# rPi_vsynth.net
KiCad netlist of a schematic drawn in EAGLE
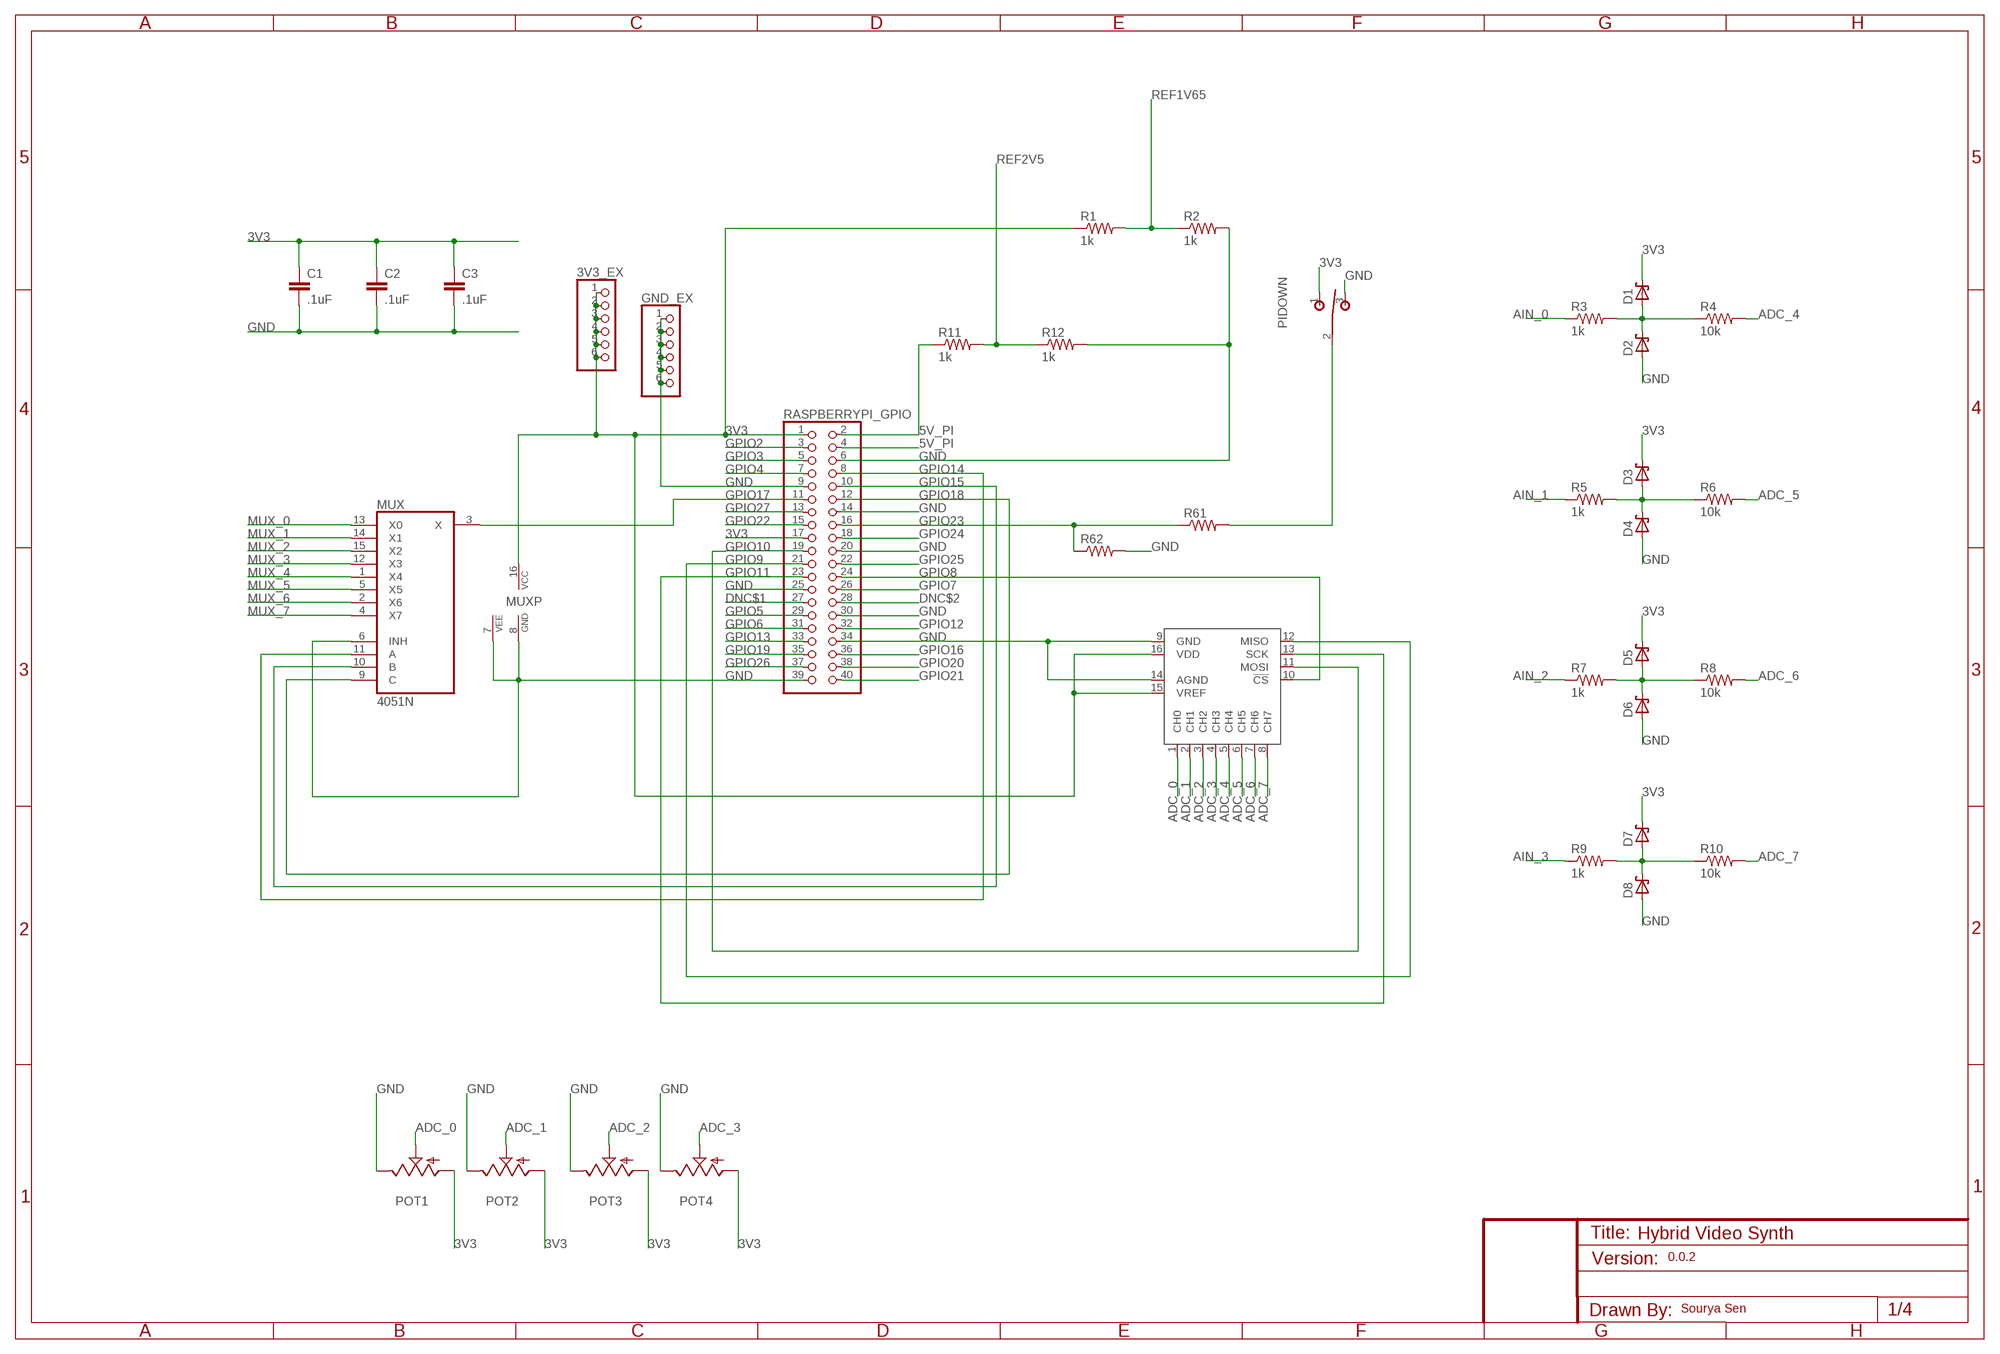
[diagram p0: schematic, sheet 1]
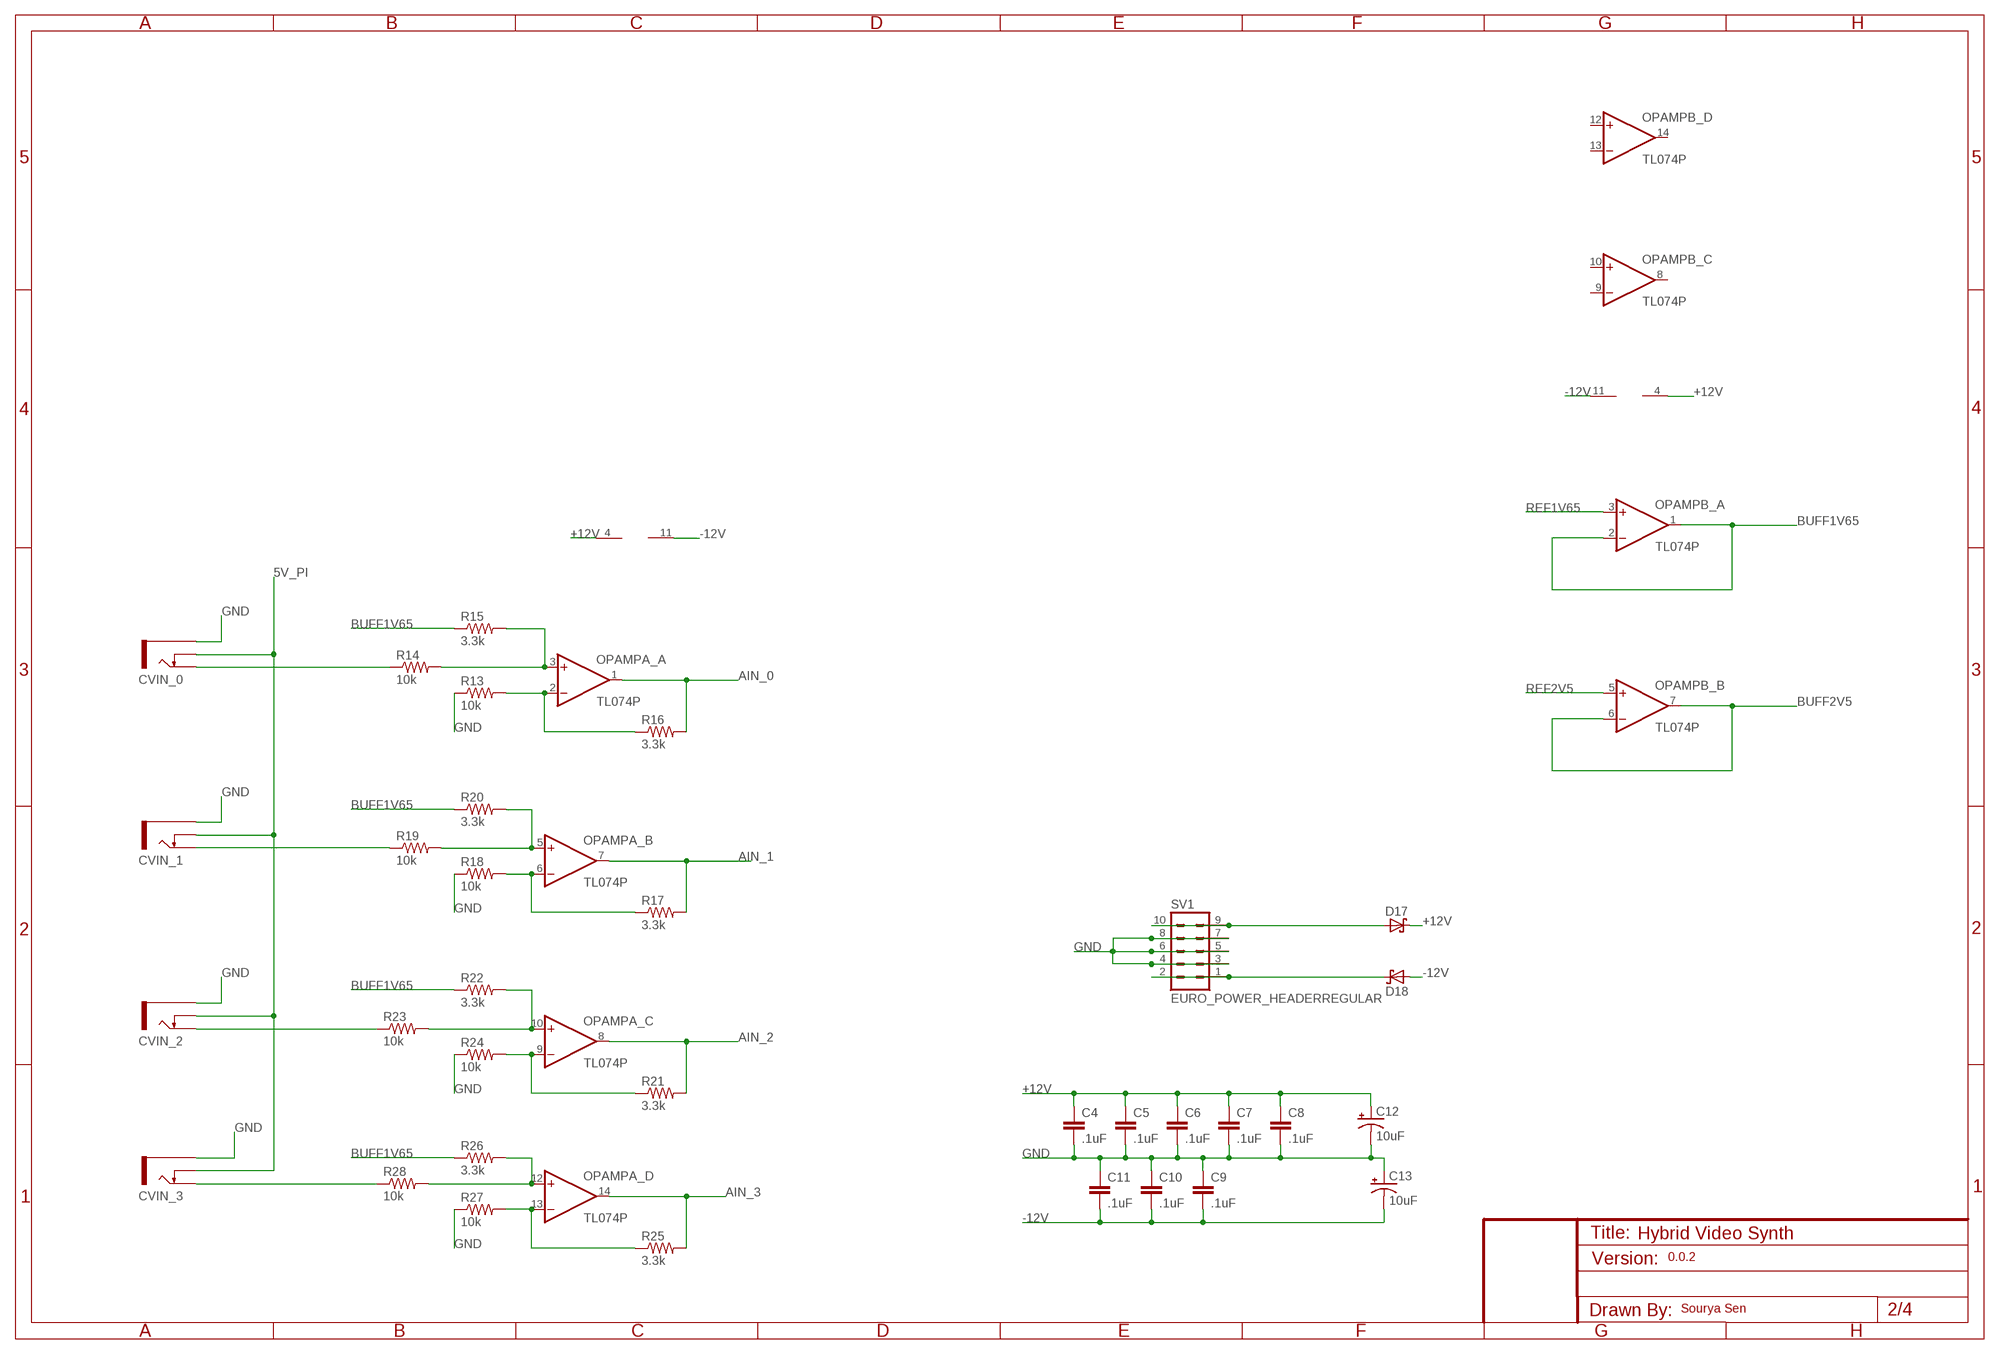
[diagram p1: schematic, sheet 2]
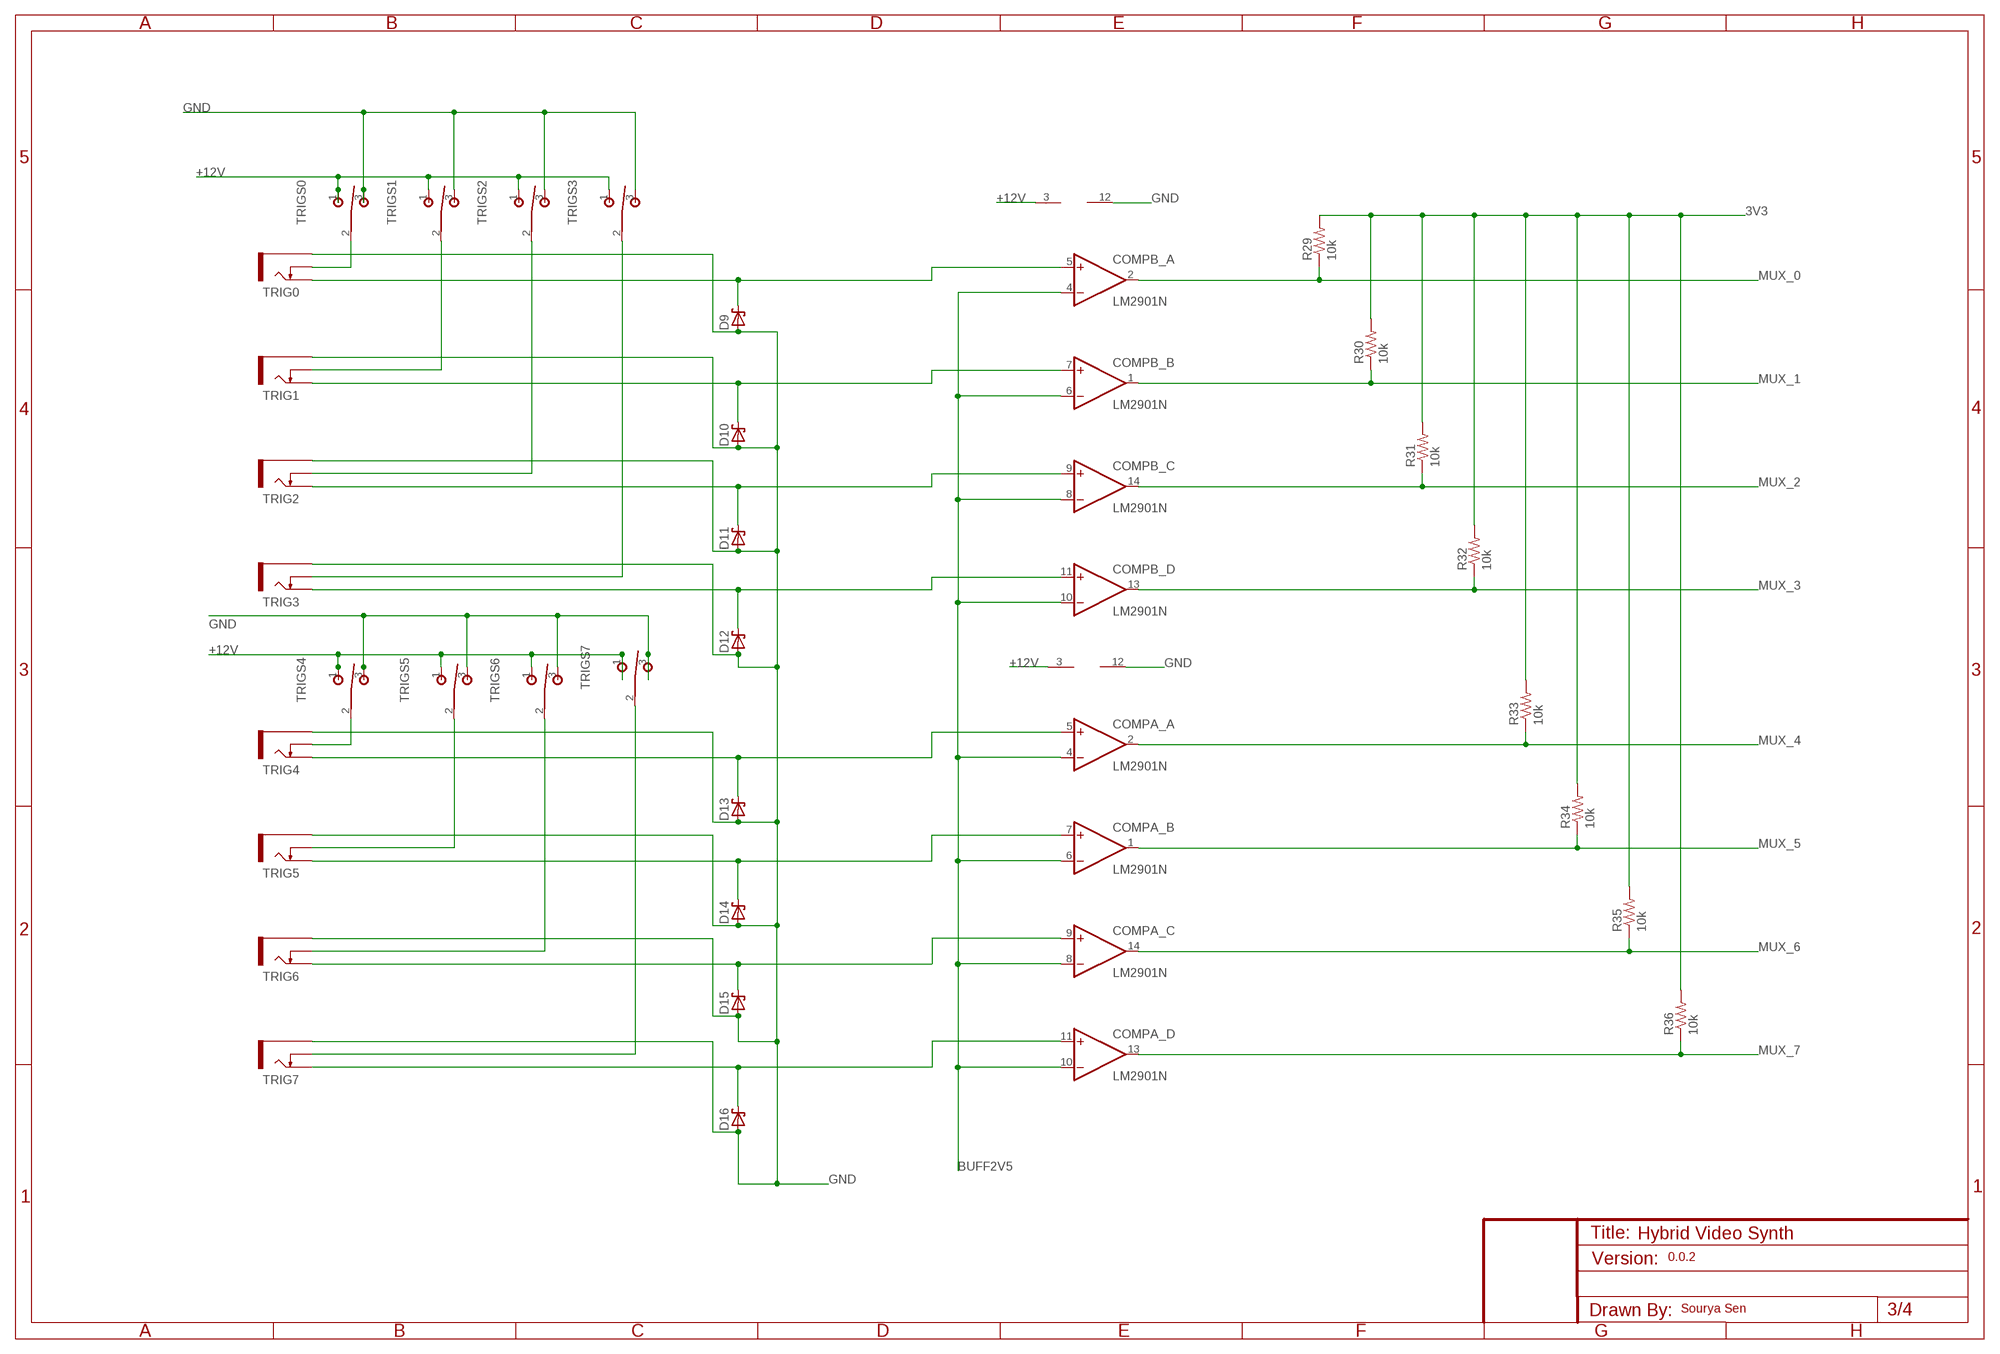
[diagram p2: schematic, sheet 3]
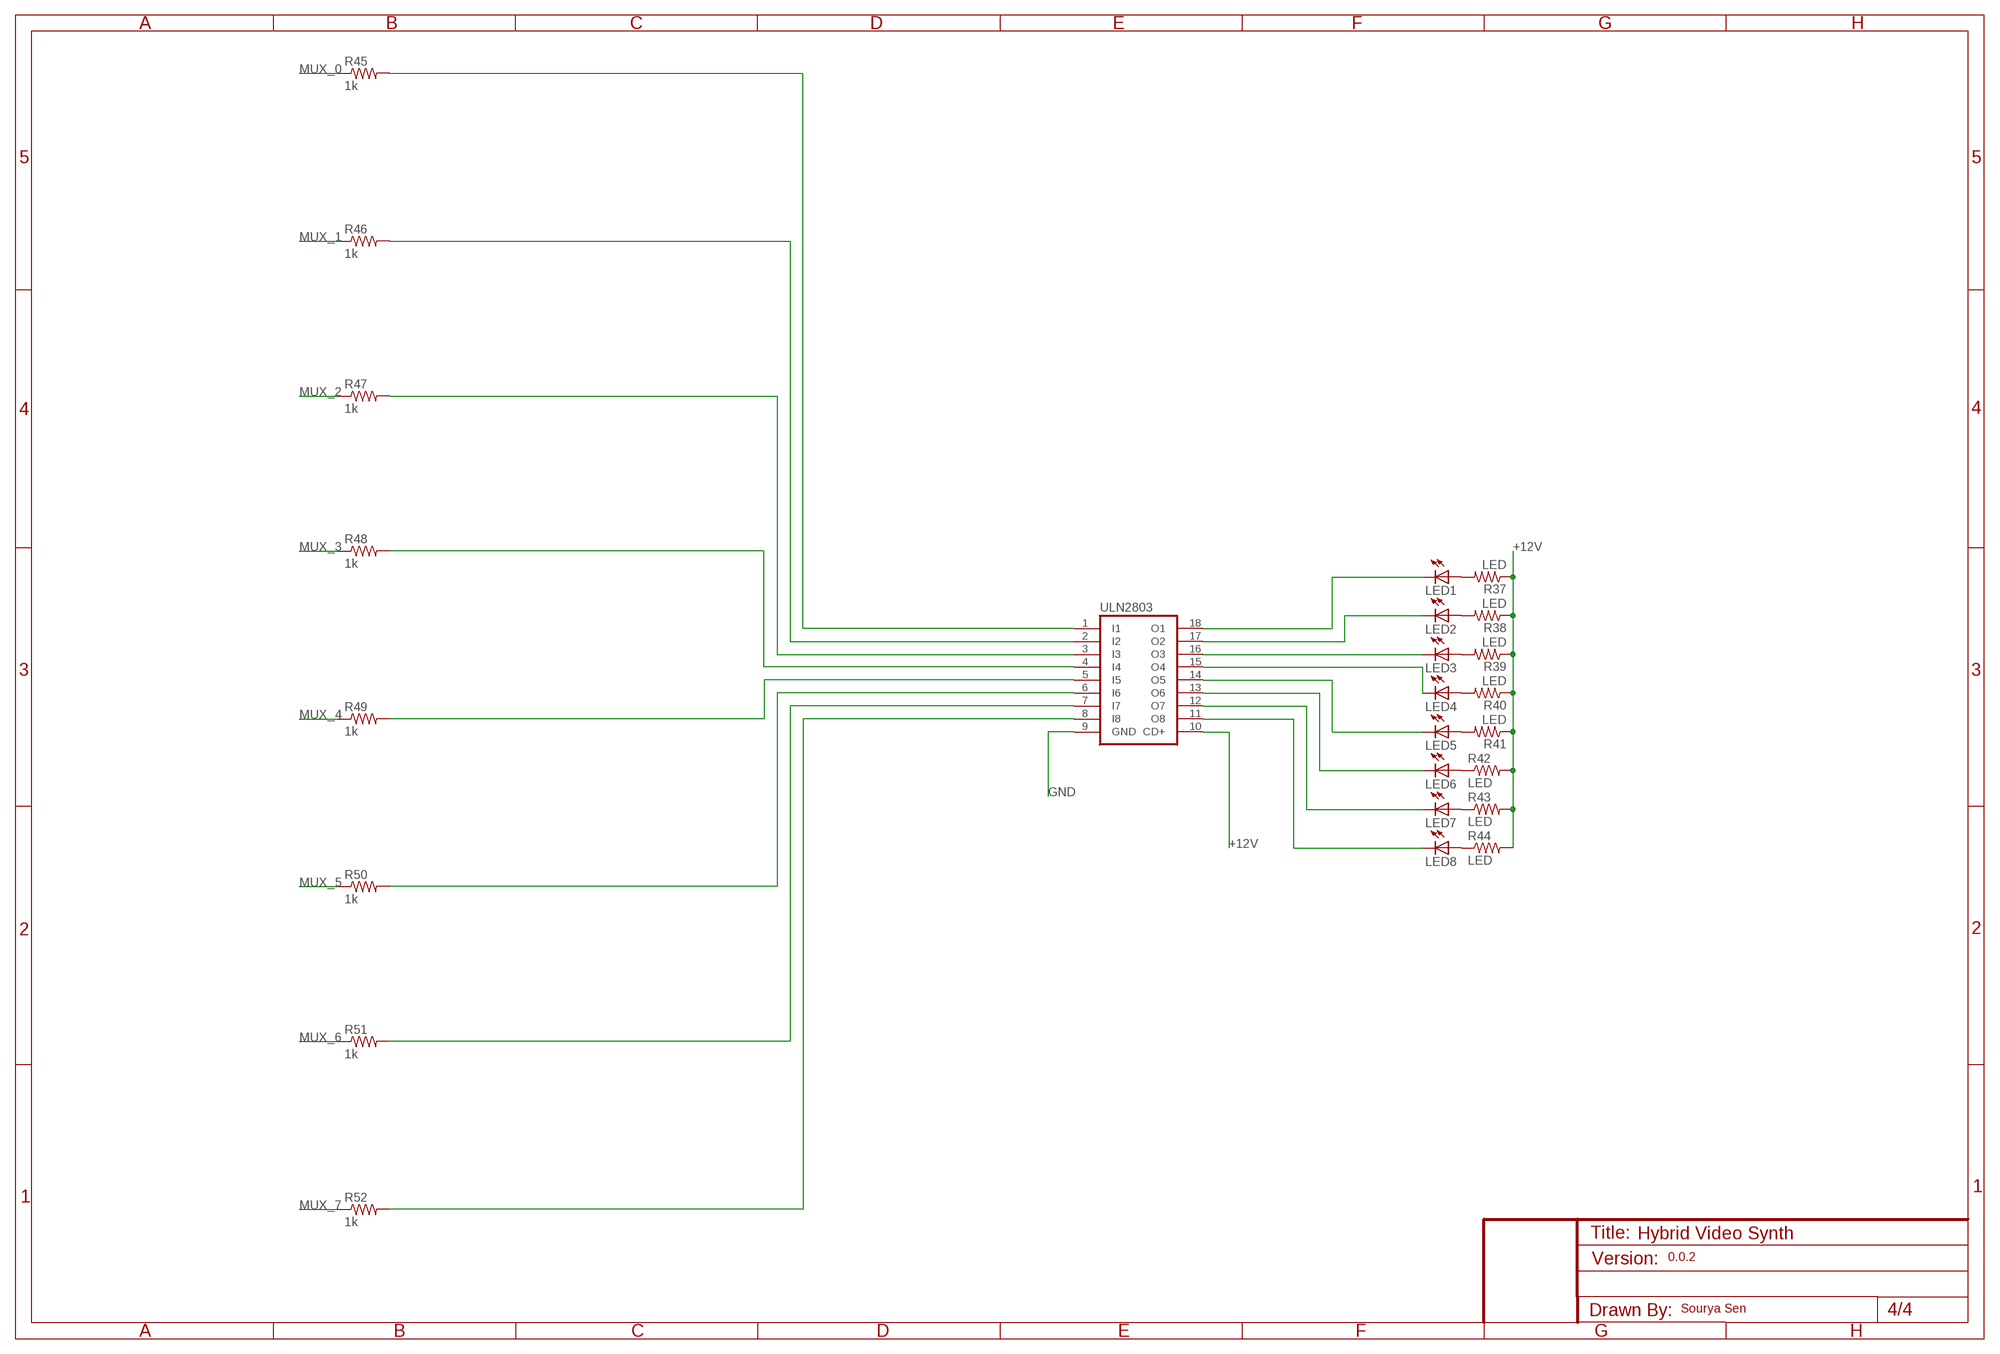
[diagram p3: schematic, sheet 4]

(export (version "E")
  (design (tool "Eeschema 10.0.6"))
  (components
    (comp (ref "3V3_EX")
      (value "PINHD-1X6B")
      (footprint "eagle-import:1X06-BIG")
      (libsource (lib "eagle-import") (part "PINHD-1X6B"))
    )
    (comp (ref "C1")
      (value ".1uF")
      (footprint "eagle-import:CAP-PTH-SMALL2")
      (libsource (lib "eagle-import") (part "CAPPTH2"))
    )
    (comp (ref "C2")
      (value ".1uF")
      (footprint "eagle-import:CAP-PTH-SMALL2")
      (libsource (lib "eagle-import") (part "CAPPTH2"))
    )
    (comp (ref "C3")
      (value ".1uF")
      (footprint "eagle-import:CAP-PTH-SMALL2")
      (libsource (lib "eagle-import") (part "CAPPTH2"))
    )
    (comp (ref "D1")
      (value "SCHOTTKY-DIODEDO35-7")
      (footprint "eagle-import:DO35-7")
      (libsource (lib "eagle-import") (part "SCHOTTKY-DIODEDO35-7"))
    )
    (comp (ref "D2")
      (value "SCHOTTKY-DIODEDO35-7")
      (footprint "eagle-import:DO35-7")
      (libsource (lib "eagle-import") (part "SCHOTTKY-DIODEDO35-7"))
    )
    (comp (ref "D3")
      (value "SCHOTTKY-DIODEDO35-7")
      (footprint "eagle-import:DO35-7")
      (libsource (lib "eagle-import") (part "SCHOTTKY-DIODEDO35-7"))
    )
    (comp (ref "D4")
      (value "SCHOTTKY-DIODEDO35-7")
      (footprint "eagle-import:DO35-7")
      (libsource (lib "eagle-import") (part "SCHOTTKY-DIODEDO35-7"))
    )
    (comp (ref "D5")
      (value "SCHOTTKY-DIODEDO35-7")
      (footprint "eagle-import:DO35-7")
      (libsource (lib "eagle-import") (part "SCHOTTKY-DIODEDO35-7"))
    )
    (comp (ref "D6")
      (value "SCHOTTKY-DIODEDO35-7")
      (footprint "eagle-import:DO35-7")
      (libsource (lib "eagle-import") (part "SCHOTTKY-DIODEDO35-7"))
    )
    (comp (ref "D7")
      (value "SCHOTTKY-DIODEDO35-7")
      (footprint "eagle-import:DO35-7")
      (libsource (lib "eagle-import") (part "SCHOTTKY-DIODEDO35-7"))
    )
    (comp (ref "D8")
      (value "SCHOTTKY-DIODEDO35-7")
      (footprint "eagle-import:DO35-7")
      (libsource (lib "eagle-import") (part "SCHOTTKY-DIODEDO35-7"))
    )
    (comp (ref "GND_EX")
      (value "PINHD-1X6B")
      (footprint "eagle-import:1X06-BIG")
      (libsource (lib "eagle-import") (part "PINHD-1X6B"))
    )
    (comp (ref "MCP3008")
      (value "MCP3008P")
      (footprint "eagle-import:DIL16")
      (libsource (lib "eagle-import") (part "MCP3008P"))
    )
    (comp (ref "MUX")
      (value "4051N")
      (footprint "eagle-import:DIL16")
      (libsource (lib "eagle-import") (part "4051N"))
    )
    (comp (ref "PIDOWN")
      (value "T-80-T-SPDT-ON-OFF-ON")
      (footprint "eagle-import:M9040P")
      (libsource (lib "eagle-import") (part "T-80-T-SPDT-ON-OFF-ON"))
    )
    (comp (ref "POT1")
      (value "9MM_SNAP-IN_POT_")
      (footprint "eagle-import:9MM_SNAP-IN_POT")
      (libsource (lib "eagle-import") (part "9MM_SNAP-IN_POT_"))
    )
    (comp (ref "POT2")
      (value "9MM_SNAP-IN_POT_")
      (footprint "eagle-import:9MM_SNAP-IN_POT")
      (libsource (lib "eagle-import") (part "9MM_SNAP-IN_POT_"))
    )
    (comp (ref "POT3")
      (value "9MM_SNAP-IN_POT_")
      (footprint "eagle-import:9MM_SNAP-IN_POT")
      (libsource (lib "eagle-import") (part "9MM_SNAP-IN_POT_"))
    )
    (comp (ref "POT4")
      (value "9MM_SNAP-IN_POT_")
      (footprint "eagle-import:9MM_SNAP-IN_POT")
      (libsource (lib "eagle-import") (part "9MM_SNAP-IN_POT_"))
    )
    (comp (ref "R1")
      (value "1k")
      (footprint "eagle-import:AXIAL-0.4")
      (libsource (lib "eagle-import") (part "RESISTORPTH-1/4W"))
    )
    (comp (ref "R2")
      (value "1k")
      (footprint "eagle-import:AXIAL-0.4")
      (libsource (lib "eagle-import") (part "RESISTORPTH-1/4W"))
    )
    (comp (ref "R3")
      (value "1k")
      (footprint "eagle-import:AXIAL-0.4")
      (libsource (lib "eagle-import") (part "RESISTORPTH-1/4W"))
    )
    (comp (ref "R4")
      (value "10k")
      (footprint "eagle-import:AXIAL-0.4")
      (libsource (lib "eagle-import") (part "RESISTORPTH-1/4W"))
    )
    (comp (ref "R5")
      (value "1k")
      (footprint "eagle-import:AXIAL-0.4")
      (libsource (lib "eagle-import") (part "RESISTORPTH-1/4W"))
    )
    (comp (ref "R6")
      (value "10k")
      (footprint "eagle-import:AXIAL-0.4")
      (libsource (lib "eagle-import") (part "RESISTORPTH-1/4W"))
    )
    (comp (ref "R7")
      (value "1k")
      (footprint "eagle-import:AXIAL-0.4")
      (libsource (lib "eagle-import") (part "RESISTORPTH-1/4W"))
    )
    (comp (ref "R8")
      (value "10k")
      (footprint "eagle-import:AXIAL-0.4")
      (libsource (lib "eagle-import") (part "RESISTORPTH-1/4W"))
    )
    (comp (ref "R9")
      (value "1k")
      (footprint "eagle-import:AXIAL-0.4")
      (libsource (lib "eagle-import") (part "RESISTORPTH-1/4W"))
    )
    (comp (ref "R10")
      (value "10k")
      (footprint "eagle-import:AXIAL-0.4")
      (libsource (lib "eagle-import") (part "RESISTORPTH-1/4W"))
    )
    (comp (ref "R11")
      (value "1k")
      (footprint "eagle-import:AXIAL-0.4")
      (libsource (lib "eagle-import") (part "RESISTORPTH-1/4W"))
    )
    (comp (ref "R12")
      (value "1k")
      (footprint "eagle-import:AXIAL-0.4")
      (libsource (lib "eagle-import") (part "RESISTORPTH-1/4W"))
    )
    (comp (ref "R61")
      (value "RESISTORPTH-1/4W")
      (footprint "eagle-import:AXIAL-0.4")
      (libsource (lib "eagle-import") (part "RESISTORPTH-1/4W"))
    )
    (comp (ref "R62")
      (value "RESISTORPTH-1/4W")
      (footprint "eagle-import:AXIAL-0.4")
      (libsource (lib "eagle-import") (part "RESISTORPTH-1/4W"))
    )
    (comp (ref "RASPBERRYPI_GPIO")
      (value "PINHD-2X20")
      (footprint "eagle-import:2X20")
      (libsource (lib "eagle-import") (part "PINHD-2X20"))
    )
    (comp (ref "C4")
      (value ".1uF")
      (footprint "eagle-import:CAP-PTH-SMALL2")
      (libsource (lib "eagle-import") (part "CAPPTH2"))
    )
    (comp (ref "C5")
      (value ".1uF")
      (footprint "eagle-import:CAP-PTH-SMALL2")
      (libsource (lib "eagle-import") (part "CAPPTH2"))
    )
    (comp (ref "C6")
      (value ".1uF")
      (footprint "eagle-import:CAP-PTH-SMALL2")
      (libsource (lib "eagle-import") (part "CAPPTH2"))
    )
    (comp (ref "C7")
      (value ".1uF")
      (footprint "eagle-import:CAP-PTH-SMALL2")
      (libsource (lib "eagle-import") (part "CAPPTH2"))
    )
    (comp (ref "C8")
      (value ".1uF")
      (footprint "eagle-import:CAP-PTH-SMALL2")
      (libsource (lib "eagle-import") (part "CAPPTH2"))
    )
    (comp (ref "C9")
      (value ".1uF")
      (footprint "eagle-import:CAP-PTH-SMALL2")
      (libsource (lib "eagle-import") (part "CAPPTH2"))
    )
    (comp (ref "C10")
      (value ".1uF")
      (footprint "eagle-import:CAP-PTH-SMALL2")
      (libsource (lib "eagle-import") (part "CAPPTH2"))
    )
    (comp (ref "C11")
      (value ".1uF")
      (footprint "eagle-import:CAP-PTH-SMALL2")
      (libsource (lib "eagle-import") (part "CAPPTH2"))
    )
    (comp (ref "C12")
      (value "10uF")
      (footprint "eagle-import:CPOL-RADIAL-10UF-25V")
      (libsource (lib "eagle-import") (part "CAP_POLPTH2"))
    )
    (comp (ref "C13")
      (value "10uF")
      (footprint "eagle-import:CPOL-RADIAL-10UF-25V")
      (libsource (lib "eagle-import") (part "CAP_POLPTH2"))
    )
    (comp (ref "CVIN_0")
      (value "THONKICONNOLD")
      (footprint "eagle-import:THONKICONN")
      (libsource (lib "eagle-import") (part "THONKICONNOLD"))
    )
    (comp (ref "CVIN_1")
      (value "THONKICONNOLD")
      (footprint "eagle-import:THONKICONN")
      (libsource (lib "eagle-import") (part "THONKICONNOLD"))
    )
    (comp (ref "CVIN_2")
      (value "THONKICONNOLD")
      (footprint "eagle-import:THONKICONN")
      (libsource (lib "eagle-import") (part "THONKICONNOLD"))
    )
    (comp (ref "CVIN_3")
      (value "THONKICONNOLD")
      (footprint "eagle-import:THONKICONN")
      (libsource (lib "eagle-import") (part "THONKICONNOLD"))
    )
    (comp (ref "D17")
      (value "SCHOTTKY-DIODEDO35-7")
      (footprint "eagle-import:DO35-7")
      (libsource (lib "eagle-import") (part "SCHOTTKY-DIODEDO35-7"))
    )
    (comp (ref "D18")
      (value "SCHOTTKY-DIODEDO35-7")
      (footprint "eagle-import:DO35-7")
      (libsource (lib "eagle-import") (part "SCHOTTKY-DIODEDO35-7"))
    )
    (comp (ref "OPAMPA_")
      (value "TL074P")
      (footprint "eagle-import:DIL14")
      (libsource (lib "eagle-import") (part "TL074P"))
    )
    (comp (ref "OPAMPB_")
      (value "TL074P")
      (footprint "eagle-import:DIL14")
      (libsource (lib "eagle-import") (part "TL074P"))
    )
    (comp (ref "R13")
      (value "10k")
      (footprint "eagle-import:AXIAL-0.4")
      (libsource (lib "eagle-import") (part "RESISTORPTH-1/4W"))
    )
    (comp (ref "R14")
      (value "10k")
      (footprint "eagle-import:AXIAL-0.4")
      (libsource (lib "eagle-import") (part "RESISTORPTH-1/4W"))
    )
    (comp (ref "R15")
      (value "3.3k")
      (footprint "eagle-import:AXIAL-0.4")
      (libsource (lib "eagle-import") (part "RESISTORPTH-1/4W"))
    )
    (comp (ref "R16")
      (value "3.3k")
      (footprint "eagle-import:AXIAL-0.4")
      (libsource (lib "eagle-import") (part "RESISTORPTH-1/4W"))
    )
    (comp (ref "R17")
      (value "3.3k")
      (footprint "eagle-import:AXIAL-0.4")
      (libsource (lib "eagle-import") (part "RESISTORPTH-1/4W"))
    )
    (comp (ref "R18")
      (value "10k")
      (footprint "eagle-import:AXIAL-0.4")
      (libsource (lib "eagle-import") (part "RESISTORPTH-1/4W"))
    )
    (comp (ref "R19")
      (value "10k")
      (footprint "eagle-import:AXIAL-0.4")
      (libsource (lib "eagle-import") (part "RESISTORPTH-1/4W"))
    )
    (comp (ref "R20")
      (value "3.3k")
      (footprint "eagle-import:AXIAL-0.4")
      (libsource (lib "eagle-import") (part "RESISTORPTH-1/4W"))
    )
    (comp (ref "R21")
      (value "3.3k")
      (footprint "eagle-import:AXIAL-0.4")
      (libsource (lib "eagle-import") (part "RESISTORPTH-1/4W"))
    )
    (comp (ref "R22")
      (value "3.3k")
      (footprint "eagle-import:AXIAL-0.4")
      (libsource (lib "eagle-import") (part "RESISTORPTH-1/4W"))
    )
    (comp (ref "R23")
      (value "10k")
      (footprint "eagle-import:AXIAL-0.4")
      (libsource (lib "eagle-import") (part "RESISTORPTH-1/4W"))
    )
    (comp (ref "R24")
      (value "10k")
      (footprint "eagle-import:AXIAL-0.4")
      (libsource (lib "eagle-import") (part "RESISTORPTH-1/4W"))
    )
    (comp (ref "R25")
      (value "3.3k")
      (footprint "eagle-import:AXIAL-0.4")
      (libsource (lib "eagle-import") (part "RESISTORPTH-1/4W"))
    )
    (comp (ref "R26")
      (value "3.3k")
      (footprint "eagle-import:AXIAL-0.4")
      (libsource (lib "eagle-import") (part "RESISTORPTH-1/4W"))
    )
    (comp (ref "R27")
      (value "10k")
      (footprint "eagle-import:AXIAL-0.4")
      (libsource (lib "eagle-import") (part "RESISTORPTH-1/4W"))
    )
    (comp (ref "R28")
      (value "10k")
      (footprint "eagle-import:AXIAL-0.4")
      (libsource (lib "eagle-import") (part "RESISTORPTH-1/4W"))
    )
    (comp (ref "SV1")
      (value "EURO_POWER_HEADERREGULAR")
      (footprint "eagle-import:EURO_POWER_HEADER")
      (libsource (lib "eagle-import") (part "EURO_POWER_HEADERREGULAR"))
    )
    (comp (ref "COMPA_")
      (value "LM2901N")
      (footprint "eagle-import:DIL14")
      (libsource (lib "eagle-import") (part "LM2901N"))
    )
    (comp (ref "COMPB_")
      (value "LM2901N")
      (footprint "eagle-import:DIL14")
      (libsource (lib "eagle-import") (part "LM2901N"))
    )
    (comp (ref "D9")
      (value "SCHOTTKY-DIODEDO35-7")
      (footprint "eagle-import:DO35-7")
      (libsource (lib "eagle-import") (part "SCHOTTKY-DIODEDO35-7"))
    )
    (comp (ref "D10")
      (value "SCHOTTKY-DIODEDO35-7")
      (footprint "eagle-import:DO35-7")
      (libsource (lib "eagle-import") (part "SCHOTTKY-DIODEDO35-7"))
    )
    (comp (ref "D11")
      (value "SCHOTTKY-DIODEDO35-7")
      (footprint "eagle-import:DO35-7")
      (libsource (lib "eagle-import") (part "SCHOTTKY-DIODEDO35-7"))
    )
    (comp (ref "D12")
      (value "SCHOTTKY-DIODEDO35-7")
      (footprint "eagle-import:DO35-7")
      (libsource (lib "eagle-import") (part "SCHOTTKY-DIODEDO35-7"))
    )
    (comp (ref "D13")
      (value "SCHOTTKY-DIODEDO35-7")
      (footprint "eagle-import:DO35-7")
      (libsource (lib "eagle-import") (part "SCHOTTKY-DIODEDO35-7"))
    )
    (comp (ref "D14")
      (value "SCHOTTKY-DIODEDO35-7")
      (footprint "eagle-import:DO35-7")
      (libsource (lib "eagle-import") (part "SCHOTTKY-DIODEDO35-7"))
    )
    (comp (ref "D15")
      (value "SCHOTTKY-DIODEDO35-7")
      (footprint "eagle-import:DO35-7")
      (libsource (lib "eagle-import") (part "SCHOTTKY-DIODEDO35-7"))
    )
    (comp (ref "D16")
      (value "SCHOTTKY-DIODEDO35-7")
      (footprint "eagle-import:DO35-7")
      (libsource (lib "eagle-import") (part "SCHOTTKY-DIODEDO35-7"))
    )
    (comp (ref "R29")
      (value "10k")
      (footprint "eagle-import:AXIAL-0.4")
      (libsource (lib "eagle-import") (part "RESISTORPTH-1/4W"))
    )
    (comp (ref "R30")
      (value "10k")
      (footprint "eagle-import:AXIAL-0.4")
      (libsource (lib "eagle-import") (part "RESISTORPTH-1/4W"))
    )
    (comp (ref "R31")
      (value "10k")
      (footprint "eagle-import:AXIAL-0.4")
      (libsource (lib "eagle-import") (part "RESISTORPTH-1/4W"))
    )
    (comp (ref "R32")
      (value "10k")
      (footprint "eagle-import:AXIAL-0.4")
      (libsource (lib "eagle-import") (part "RESISTORPTH-1/4W"))
    )
    (comp (ref "R33")
      (value "10k")
      (footprint "eagle-import:AXIAL-0.4")
      (libsource (lib "eagle-import") (part "RESISTORPTH-1/4W"))
    )
    (comp (ref "R34")
      (value "10k")
      (footprint "eagle-import:AXIAL-0.4")
      (libsource (lib "eagle-import") (part "RESISTORPTH-1/4W"))
    )
    (comp (ref "R35")
      (value "10k")
      (footprint "eagle-import:AXIAL-0.4")
      (libsource (lib "eagle-import") (part "RESISTORPTH-1/4W"))
    )
    (comp (ref "R36")
      (value "10k")
      (footprint "eagle-import:AXIAL-0.4")
      (libsource (lib "eagle-import") (part "RESISTORPTH-1/4W"))
    )
    (comp (ref "TRIG0")
      (value "THONKICONNOLD")
      (footprint "eagle-import:THONKICONN")
      (libsource (lib "eagle-import") (part "THONKICONNOLD"))
    )
    (comp (ref "TRIG1")
      (value "THONKICONNOLD")
      (footprint "eagle-import:THONKICONN")
      (libsource (lib "eagle-import") (part "THONKICONNOLD"))
    )
    (comp (ref "TRIG2")
      (value "THONKICONNOLD")
      (footprint "eagle-import:THONKICONN")
      (libsource (lib "eagle-import") (part "THONKICONNOLD"))
    )
    (comp (ref "TRIG3")
      (value "THONKICONNOLD")
      (footprint "eagle-import:THONKICONN")
      (libsource (lib "eagle-import") (part "THONKICONNOLD"))
    )
    (comp (ref "TRIG4")
      (value "THONKICONNOLD")
      (footprint "eagle-import:THONKICONN")
      (libsource (lib "eagle-import") (part "THONKICONNOLD"))
    )
    (comp (ref "TRIG5")
      (value "THONKICONNOLD")
      (footprint "eagle-import:THONKICONN")
      (libsource (lib "eagle-import") (part "THONKICONNOLD"))
    )
    (comp (ref "TRIG6")
      (value "THONKICONNOLD")
      (footprint "eagle-import:THONKICONN")
      (libsource (lib "eagle-import") (part "THONKICONNOLD"))
    )
    (comp (ref "TRIG7")
      (value "THONKICONNOLD")
      (footprint "eagle-import:THONKICONN")
      (libsource (lib "eagle-import") (part "THONKICONNOLD"))
    )
    (comp (ref "TRIGS0")
      (value "T-80-T-SPDT-ON-OFF-ON")
      (footprint "eagle-import:M9040P")
      (libsource (lib "eagle-import") (part "T-80-T-SPDT-ON-OFF-ON"))
    )
    (comp (ref "TRIGS1")
      (value "T-80-T-SPDT-ON-OFF-ON")
      (footprint "eagle-import:M9040P")
      (libsource (lib "eagle-import") (part "T-80-T-SPDT-ON-OFF-ON"))
    )
    (comp (ref "TRIGS2")
      (value "T-80-T-SPDT-ON-OFF-ON")
      (footprint "eagle-import:M9040P")
      (libsource (lib "eagle-import") (part "T-80-T-SPDT-ON-OFF-ON"))
    )
    (comp (ref "TRIGS3")
      (value "T-80-T-SPDT-ON-OFF-ON")
      (footprint "eagle-import:M9040P")
      (libsource (lib "eagle-import") (part "T-80-T-SPDT-ON-OFF-ON"))
    )
    (comp (ref "TRIGS4")
      (value "T-80-T-SPDT-ON-OFF-ON")
      (footprint "eagle-import:M9040P")
      (libsource (lib "eagle-import") (part "T-80-T-SPDT-ON-OFF-ON"))
    )
    (comp (ref "TRIGS5")
      (value "T-80-T-SPDT-ON-OFF-ON")
      (footprint "eagle-import:M9040P")
      (libsource (lib "eagle-import") (part "T-80-T-SPDT-ON-OFF-ON"))
    )
    (comp (ref "TRIGS6")
      (value "T-80-T-SPDT-ON-OFF-ON")
      (footprint "eagle-import:M9040P")
      (libsource (lib "eagle-import") (part "T-80-T-SPDT-ON-OFF-ON"))
    )
    (comp (ref "TRIGS7")
      (value "T-80-T-SPDT-ON-OFF-ON")
      (footprint "eagle-import:M9040P")
      (libsource (lib "eagle-import") (part "T-80-T-SPDT-ON-OFF-ON"))
    )
    (comp (ref "LED1")
      (value "LED3MM")
      (footprint "eagle-import:LED3MM")
      (libsource (lib "eagle-import") (part "LED3MM"))
    )
    (comp (ref "LED2")
      (value "LED3MM")
      (footprint "eagle-import:LED3MM")
      (libsource (lib "eagle-import") (part "LED3MM"))
    )
    (comp (ref "LED3")
      (value "LED3MM")
      (footprint "eagle-import:LED3MM")
      (libsource (lib "eagle-import") (part "LED3MM"))
    )
    (comp (ref "LED4")
      (value "LED3MM")
      (footprint "eagle-import:LED3MM")
      (libsource (lib "eagle-import") (part "LED3MM"))
    )
    (comp (ref "LED5")
      (value "LED3MM")
      (footprint "eagle-import:LED3MM")
      (libsource (lib "eagle-import") (part "LED3MM"))
    )
    (comp (ref "LED6")
      (value "LED3MM")
      (footprint "eagle-import:LED3MM")
      (libsource (lib "eagle-import") (part "LED3MM"))
    )
    (comp (ref "LED7")
      (value "LED3MM")
      (footprint "eagle-import:LED3MM")
      (libsource (lib "eagle-import") (part "LED3MM"))
    )
    (comp (ref "LED8")
      (value "LED3MM")
      (footprint "eagle-import:LED3MM")
      (libsource (lib "eagle-import") (part "LED3MM"))
    )
    (comp (ref "R37")
      (value "LED")
      (footprint "eagle-import:AXIAL-0.4")
      (libsource (lib "eagle-import") (part "RESISTORPTH-1/4W"))
    )
    (comp (ref "R38")
      (value "LED")
      (footprint "eagle-import:AXIAL-0.4")
      (libsource (lib "eagle-import") (part "RESISTORPTH-1/4W"))
    )
    (comp (ref "R39")
      (value "LED")
      (footprint "eagle-import:AXIAL-0.4")
      (libsource (lib "eagle-import") (part "RESISTORPTH-1/4W"))
    )
    (comp (ref "R40")
      (value "LED")
      (footprint "eagle-import:AXIAL-0.4")
      (libsource (lib "eagle-import") (part "RESISTORPTH-1/4W"))
    )
    (comp (ref "R41")
      (value "LED")
      (footprint "eagle-import:AXIAL-0.4")
      (libsource (lib "eagle-import") (part "RESISTORPTH-1/4W"))
    )
    (comp (ref "R42")
      (value "LED")
      (footprint "eagle-import:AXIAL-0.4")
      (libsource (lib "eagle-import") (part "RESISTORPTH-1/4W"))
    )
    (comp (ref "R43")
      (value "LED")
      (footprint "eagle-import:AXIAL-0.4")
      (libsource (lib "eagle-import") (part "RESISTORPTH-1/4W"))
    )
    (comp (ref "R44")
      (value "LED")
      (footprint "eagle-import:AXIAL-0.4")
      (libsource (lib "eagle-import") (part "RESISTORPTH-1/4W"))
    )
    (comp (ref "R45")
      (value "1k")
      (footprint "eagle-import:AXIAL-0.4")
      (libsource (lib "eagle-import") (part "RESISTORPTH-1/4W"))
    )
    (comp (ref "R46")
      (value "1k")
      (footprint "eagle-import:AXIAL-0.4")
      (libsource (lib "eagle-import") (part "RESISTORPTH-1/4W"))
    )
    (comp (ref "R47")
      (value "1k")
      (footprint "eagle-import:AXIAL-0.4")
      (libsource (lib "eagle-import") (part "RESISTORPTH-1/4W"))
    )
    (comp (ref "R48")
      (value "1k")
      (footprint "eagle-import:AXIAL-0.4")
      (libsource (lib "eagle-import") (part "RESISTORPTH-1/4W"))
    )
    (comp (ref "R49")
      (value "1k")
      (footprint "eagle-import:AXIAL-0.4")
      (libsource (lib "eagle-import") (part "RESISTORPTH-1/4W"))
    )
    (comp (ref "R50")
      (value "1k")
      (footprint "eagle-import:AXIAL-0.4")
      (libsource (lib "eagle-import") (part "RESISTORPTH-1/4W"))
    )
    (comp (ref "R51")
      (value "1k")
      (footprint "eagle-import:AXIAL-0.4")
      (libsource (lib "eagle-import") (part "RESISTORPTH-1/4W"))
    )
    (comp (ref "R52")
      (value "1k")
      (footprint "eagle-import:AXIAL-0.4")
      (libsource (lib "eagle-import") (part "RESISTORPTH-1/4W"))
    )
    (comp (ref "ULN2803")
      (value "ULN2803A")
      (footprint "eagle-import:DIL18")
      (libsource (lib "eagle-import") (part "ULN2803A"))
    )
  )
  (nets
    (net (code "1") (name "+12V") (class "Default")
      (node (ref "C12") (pin "1") (pinfunction "+_1") (pintype "passive"))
      (node (ref "C4") (pin "1") (pinfunction "1_1") (pintype "passive"))
      (node (ref "C5") (pin "1") (pinfunction "1_1") (pintype "passive"))
      (node (ref "C6") (pin "1") (pinfunction "1_1") (pintype "passive"))
      (node (ref "C7") (pin "1") (pinfunction "1_1") (pintype "passive"))
      (node (ref "C8") (pin "1") (pinfunction "1_1") (pintype "passive"))
      (node (ref "COMPA_") (pin "3") (pinfunction "V+_3") (pintype "power_in"))
      (node (ref "COMPB_") (pin "3") (pinfunction "V+_3") (pintype "power_in"))
      (node (ref "D17") (pin "C") (pinfunction "C_C") (pintype "passive"))
      (node (ref "OPAMPA_") (pin "4") (pinfunction "V+_4") (pintype "power_in"))
      (node (ref "OPAMPB_") (pin "4") (pinfunction "V+_4") (pintype "power_in"))
      (node (ref "R37") (pin "P$1") (pinfunction "1_P$1") (pintype "passive"))
      (node (ref "R38") (pin "P$1") (pinfunction "1_P$1") (pintype "passive"))
      (node (ref "R39") (pin "P$1") (pinfunction "1_P$1") (pintype "passive"))
      (node (ref "R40") (pin "P$1") (pinfunction "1_P$1") (pintype "passive"))
      (node (ref "R41") (pin "P$1") (pinfunction "1_P$1") (pintype "passive"))
      (node (ref "R42") (pin "P$2") (pinfunction "2_P$2") (pintype "passive"))
      (node (ref "R43") (pin "P$2") (pinfunction "2_P$2") (pintype "passive"))
      (node (ref "R44") (pin "P$2") (pinfunction "2_P$2") (pintype "passive"))
      (node (ref "TRIGS0") (pin "1") (pinfunction "O_1") (pintype "passive"))
      (node (ref "TRIGS1") (pin "1") (pinfunction "O_1") (pintype "passive"))
      (node (ref "TRIGS2") (pin "1") (pinfunction "O_1") (pintype "passive"))
      (node (ref "TRIGS3") (pin "1") (pinfunction "O_1") (pintype "passive"))
      (node (ref "TRIGS4") (pin "1") (pinfunction "O_1") (pintype "passive"))
      (node (ref "TRIGS5") (pin "1") (pinfunction "O_1") (pintype "passive"))
      (node (ref "TRIGS6") (pin "1") (pinfunction "O_1") (pintype "passive"))
      (node (ref "TRIGS7") (pin "1") (pinfunction "O_1") (pintype "passive"))
      (node (ref "ULN2803") (pin "10") (pinfunction "CD+_10") (pintype "passive"))
    )
    (net (code "2") (name "-12V") (class "Default")
      (node (ref "C10") (pin "2") (pinfunction "2_2") (pintype "passive"))
      (node (ref "C11") (pin "2") (pinfunction "2_2") (pintype "passive"))
      (node (ref "C13") (pin "2") (pinfunction "-_2") (pintype "passive"))
      (node (ref "C9") (pin "2") (pinfunction "2_2") (pintype "passive"))
      (node (ref "D18") (pin "A") (pinfunction "A_A") (pintype "passive"))
      (node (ref "OPAMPA_") (pin "11") (pinfunction "V-_11") (pintype "power_in"))
      (node (ref "OPAMPB_") (pin "11") (pinfunction "V-_11") (pintype "power_in"))
    )
    (net (code "3") (name "3V3") (class "Default")
      (node (ref "3V3_EX") (pin "1") (pinfunction "1_1") (pintype "passive"))
      (node (ref "3V3_EX") (pin "2") (pinfunction "2_2") (pintype "passive"))
      (node (ref "3V3_EX") (pin "3") (pinfunction "3_3") (pintype "passive"))
      (node (ref "3V3_EX") (pin "4") (pinfunction "4_4") (pintype "passive"))
      (node (ref "3V3_EX") (pin "5") (pinfunction "5_5") (pintype "passive"))
      (node (ref "3V3_EX") (pin "6") (pinfunction "6_6") (pintype "passive"))
      (node (ref "C1") (pin "1") (pinfunction "1_1") (pintype "passive"))
      (node (ref "C2") (pin "1") (pinfunction "1_1") (pintype "passive"))
      (node (ref "C3") (pin "1") (pinfunction "1_1") (pintype "passive"))
      (node (ref "D1") (pin "C") (pinfunction "C_C") (pintype "passive"))
      (node (ref "D3") (pin "C") (pinfunction "C_C") (pintype "passive"))
      (node (ref "D5") (pin "C") (pinfunction "C_C") (pintype "passive"))
      (node (ref "D7") (pin "C") (pinfunction "C_C") (pintype "passive"))
      (node (ref "MCP3008") (pin "15") (pinfunction "VREF_15") (pintype "power_in"))
      (node (ref "MCP3008") (pin "16") (pinfunction "VDD_16") (pintype "power_in"))
      (node (ref "MUX") (pin "16") (pinfunction "VCC_16") (pintype "power_in"))
      (node (ref "PIDOWN") (pin "1") (pinfunction "O_1") (pintype "passive"))
      (node (ref "POT1") (pin "1") (pinfunction "A_1") (pintype "passive"))
      (node (ref "POT2") (pin "1") (pinfunction "A_1") (pintype "passive"))
      (node (ref "POT3") (pin "1") (pinfunction "A_1") (pintype "passive"))
      (node (ref "POT4") (pin "1") (pinfunction "A_1") (pintype "passive"))
      (node (ref "R1") (pin "P$1") (pinfunction "1_P$1") (pintype "passive"))
      (node (ref "R29") (pin "P$2") (pinfunction "2_P$2") (pintype "passive"))
      (node (ref "R30") (pin "P$2") (pinfunction "2_P$2") (pintype "passive"))
      (node (ref "R31") (pin "P$2") (pinfunction "2_P$2") (pintype "passive"))
      (node (ref "R32") (pin "P$2") (pinfunction "2_P$2") (pintype "passive"))
      (node (ref "R33") (pin "P$2") (pinfunction "2_P$2") (pintype "passive"))
      (node (ref "R34") (pin "P$2") (pinfunction "2_P$2") (pintype "passive"))
      (node (ref "R35") (pin "P$2") (pinfunction "2_P$2") (pintype "passive"))
      (node (ref "R36") (pin "P$2") (pinfunction "2_P$2") (pintype "passive"))
      (node (ref "RASPBERRYPI_GPIO") (pin "1") (pinfunction "1_1") (pintype "passive"))
      (node (ref "RASPBERRYPI_GPIO") (pin "17") (pinfunction "17_17") (pintype "passive"))
    )
    (net (code "4") (name "5V_PI") (class "Default")
      (node (ref "CVIN_0") (pin "P$2_SWITCH") (pinfunction "SWITCH_P$2_SWITCH") (pintype "passive"))
      (node (ref "CVIN_1") (pin "P$2_SWITCH") (pinfunction "SWITCH_P$2_SWITCH") (pintype "passive"))
      (node (ref "CVIN_2") (pin "P$2_SWITCH") (pinfunction "SWITCH_P$2_SWITCH") (pintype "passive"))
      (node (ref "CVIN_3") (pin "P$2_SWITCH") (pinfunction "SWITCH_P$2_SWITCH") (pintype "passive"))
      (node (ref "R11") (pin "P$1") (pinfunction "1_P$1") (pintype "passive"))
      (node (ref "RASPBERRYPI_GPIO") (pin "2") (pinfunction "2_2") (pintype "passive"))
      (node (ref "RASPBERRYPI_GPIO") (pin "4") (pinfunction "4_4") (pintype "passive"))
    )
    (net (code "5") (name "ADC_0") (class "Default")
      (node (ref "MCP3008") (pin "1") (pinfunction "CH0_1") (pintype "input"))
      (node (ref "POT1") (pin "2") (pinfunction "S_2") (pintype "passive"))
    )
    (net (code "6") (name "ADC_1") (class "Default")
      (node (ref "MCP3008") (pin "2") (pinfunction "CH1_2") (pintype "input"))
      (node (ref "POT2") (pin "2") (pinfunction "S_2") (pintype "passive"))
    )
    (net (code "7") (name "ADC_2") (class "Default")
      (node (ref "MCP3008") (pin "3") (pinfunction "CH2_3") (pintype "input"))
      (node (ref "POT3") (pin "2") (pinfunction "S_2") (pintype "passive"))
    )
    (net (code "8") (name "ADC_3") (class "Default")
      (node (ref "MCP3008") (pin "4") (pinfunction "CH3_4") (pintype "input"))
      (node (ref "POT4") (pin "2") (pinfunction "S_2") (pintype "passive"))
    )
    (net (code "9") (name "ADC_4") (class "Default")
      (node (ref "MCP3008") (pin "5") (pinfunction "CH4_5") (pintype "input"))
      (node (ref "R4") (pin "P$2") (pinfunction "2_P$2") (pintype "passive"))
    )
    (net (code "10") (name "ADC_5") (class "Default")
      (node (ref "MCP3008") (pin "6") (pinfunction "CH5_6") (pintype "input"))
      (node (ref "R6") (pin "P$2") (pinfunction "2_P$2") (pintype "passive"))
    )
    (net (code "11") (name "ADC_6") (class "Default")
      (node (ref "MCP3008") (pin "7") (pinfunction "CH6_7") (pintype "input"))
      (node (ref "R8") (pin "P$2") (pinfunction "2_P$2") (pintype "passive"))
    )
    (net (code "12") (name "ADC_7") (class "Default")
      (node (ref "MCP3008") (pin "8") (pinfunction "CH7_8") (pintype "input"))
      (node (ref "R10") (pin "P$2") (pinfunction "2_P$2") (pintype "passive"))
    )
    (net (code "13") (name "AIN_0") (class "Default")
      (node (ref "OPAMPA_") (pin "1") (pinfunction "OUT_1") (pintype "output"))
      (node (ref "R16") (pin "P$2") (pinfunction "2_P$2") (pintype "passive"))
      (node (ref "R3") (pin "P$1") (pinfunction "1_P$1") (pintype "passive"))
    )
    (net (code "14") (name "AIN_1") (class "Default")
      (node (ref "OPAMPA_") (pin "7") (pinfunction "OUT_7") (pintype "output"))
      (node (ref "R17") (pin "P$2") (pinfunction "2_P$2") (pintype "passive"))
      (node (ref "R5") (pin "P$1") (pinfunction "1_P$1") (pintype "passive"))
    )
    (net (code "15") (name "AIN_2") (class "Default")
      (node (ref "OPAMPA_") (pin "8") (pinfunction "OUT_8") (pintype "output"))
      (node (ref "R21") (pin "P$2") (pinfunction "2_P$2") (pintype "passive"))
      (node (ref "R7") (pin "P$1") (pinfunction "1_P$1") (pintype "passive"))
    )
    (net (code "16") (name "AIN_3") (class "Default")
      (node (ref "OPAMPA_") (pin "14") (pinfunction "OUT_14") (pintype "output"))
      (node (ref "R25") (pin "P$2") (pinfunction "2_P$2") (pintype "passive"))
      (node (ref "R9") (pin "P$1") (pinfunction "1_P$1") (pintype "passive"))
    )
    (net (code "17") (name "BUFF1V65") (class "Default")
      (node (ref "OPAMPB_") (pin "1") (pinfunction "OUT_1") (pintype "output"))
      (node (ref "OPAMPB_") (pin "2") (pinfunction "-IN_2") (pintype "input"))
      (node (ref "R15") (pin "P$1") (pinfunction "1_P$1") (pintype "passive"))
      (node (ref "R20") (pin "P$1") (pinfunction "1_P$1") (pintype "passive"))
      (node (ref "R22") (pin "P$1") (pinfunction "1_P$1") (pintype "passive"))
      (node (ref "R26") (pin "P$1") (pinfunction "1_P$1") (pintype "passive"))
    )
    (net (code "18") (name "BUFF2V5") (class "Default")
      (node (ref "COMPA_") (pin "10") (pinfunction "-IN_10") (pintype "input"))
      (node (ref "COMPA_") (pin "4") (pinfunction "-IN_4") (pintype "input"))
      (node (ref "COMPA_") (pin "6") (pinfunction "-IN_6") (pintype "input"))
      (node (ref "COMPA_") (pin "8") (pinfunction "-IN_8") (pintype "input"))
      (node (ref "COMPB_") (pin "10") (pinfunction "-IN_10") (pintype "input"))
      (node (ref "COMPB_") (pin "4") (pinfunction "-IN_4") (pintype "input"))
      (node (ref "COMPB_") (pin "6") (pinfunction "-IN_6") (pintype "input"))
      (node (ref "COMPB_") (pin "8") (pinfunction "-IN_8") (pintype "input"))
      (node (ref "OPAMPB_") (pin "6") (pinfunction "-IN_6") (pintype "input"))
      (node (ref "OPAMPB_") (pin "7") (pinfunction "OUT_7") (pintype "output"))
    )
    (net (code "19") (name "DNC$1") (class "Default")
      (node (ref "RASPBERRYPI_GPIO") (pin "27") (pinfunction "27_27") (pintype "passive"))
    )
    (net (code "20") (name "DNC$2") (class "Default")
      (node (ref "RASPBERRYPI_GPIO") (pin "28") (pinfunction "28_28") (pintype "passive"))
    )
    (net (code "21") (name "GND") (class "Default")
      (node (ref "C1") (pin "2") (pinfunction "2_2") (pintype "passive"))
      (node (ref "C10") (pin "1") (pinfunction "1_1") (pintype "passive"))
      (node (ref "C11") (pin "1") (pinfunction "1_1") (pintype "passive"))
      (node (ref "C12") (pin "2") (pinfunction "-_2") (pintype "passive"))
      (node (ref "C13") (pin "1") (pinfunction "+_1") (pintype "passive"))
      (node (ref "C2") (pin "2") (pinfunction "2_2") (pintype "passive"))
      (node (ref "C3") (pin "2") (pinfunction "2_2") (pintype "passive"))
      (node (ref "C4") (pin "2") (pinfunction "2_2") (pintype "passive"))
      (node (ref "C5") (pin "2") (pinfunction "2_2") (pintype "passive"))
      (node (ref "C6") (pin "2") (pinfunction "2_2") (pintype "passive"))
      (node (ref "C7") (pin "2") (pinfunction "2_2") (pintype "passive"))
      (node (ref "C8") (pin "2") (pinfunction "2_2") (pintype "passive"))
      (node (ref "C9") (pin "1") (pinfunction "1_1") (pintype "passive"))
      (node (ref "COMPA_") (pin "12") (pinfunction "V-_12") (pintype "power_in"))
      (node (ref "COMPB_") (pin "12") (pinfunction "V-_12") (pintype "power_in"))
      (node (ref "CVIN_0") (pin "P$1_SLEEVE") (pinfunction "SLEEVE_P$1_SLEEVE") (pintype "passive"))
      (node (ref "CVIN_1") (pin "P$1_SLEEVE") (pinfunction "SLEEVE_P$1_SLEEVE") (pintype "passive"))
      (node (ref "CVIN_2") (pin "P$1_SLEEVE") (pinfunction "SLEEVE_P$1_SLEEVE") (pintype "passive"))
      (node (ref "CVIN_3") (pin "P$1_SLEEVE") (pinfunction "SLEEVE_P$1_SLEEVE") (pintype "passive"))
      (node (ref "D10") (pin "A") (pinfunction "A_A") (pintype "passive"))
      (node (ref "D11") (pin "A") (pinfunction "A_A") (pintype "passive"))
      (node (ref "D12") (pin "A") (pinfunction "A_A") (pintype "passive"))
      (node (ref "D13") (pin "A") (pinfunction "A_A") (pintype "passive"))
      (node (ref "D14") (pin "A") (pinfunction "A_A") (pintype "passive"))
      (node (ref "D15") (pin "A") (pinfunction "A_A") (pintype "passive"))
      (node (ref "D16") (pin "A") (pinfunction "A_A") (pintype "passive"))
      (node (ref "D2") (pin "A") (pinfunction "A_A") (pintype "passive"))
      (node (ref "D4") (pin "A") (pinfunction "A_A") (pintype "passive"))
      (node (ref "D6") (pin "A") (pinfunction "A_A") (pintype "passive"))
      (node (ref "D8") (pin "A") (pinfunction "A_A") (pintype "passive"))
      (node (ref "D9") (pin "A") (pinfunction "A_A") (pintype "passive"))
      (node (ref "GND_EX") (pin "1") (pinfunction "1_1") (pintype "passive"))
      (node (ref "GND_EX") (pin "2") (pinfunction "2_2") (pintype "passive"))
      (node (ref "GND_EX") (pin "3") (pinfunction "3_3") (pintype "passive"))
      (node (ref "GND_EX") (pin "4") (pinfunction "4_4") (pintype "passive"))
      (node (ref "GND_EX") (pin "5") (pinfunction "5_5") (pintype "passive"))
      (node (ref "GND_EX") (pin "6") (pinfunction "6_6") (pintype "passive"))
      (node (ref "MCP3008") (pin "14") (pinfunction "AGND_14") (pintype "power_in"))
      (node (ref "MCP3008") (pin "9") (pinfunction "GND_9") (pintype "power_in"))
      (node (ref "MUX") (pin "6") (pinfunction "INH_6") (pintype "input"))
      (node (ref "MUX") (pin "7") (pinfunction "VEE_7") (pintype "power_in"))
      (node (ref "MUX") (pin "8") (pinfunction "GND_8") (pintype "power_in"))
      (node (ref "PIDOWN") (pin "3") (pinfunction "S_3") (pintype "passive"))
      (node (ref "POT1") (pin "3") (pinfunction "E_3") (pintype "passive"))
      (node (ref "POT2") (pin "3") (pinfunction "E_3") (pintype "passive"))
      (node (ref "POT3") (pin "3") (pinfunction "E_3") (pintype "passive"))
      (node (ref "POT4") (pin "3") (pinfunction "E_3") (pintype "passive"))
      (node (ref "R12") (pin "P$2") (pinfunction "2_P$2") (pintype "passive"))
      (node (ref "R13") (pin "P$1") (pinfunction "1_P$1") (pintype "passive"))
      (node (ref "R18") (pin "P$1") (pinfunction "1_P$1") (pintype "passive"))
      (node (ref "R2") (pin "P$2") (pinfunction "2_P$2") (pintype "passive"))
      (node (ref "R24") (pin "P$1") (pinfunction "1_P$1") (pintype "passive"))
      (node (ref "R27") (pin "P$1") (pinfunction "1_P$1") (pintype "passive"))
      (node (ref "R62") (pin "P$2") (pinfunction "2_P$2") (pintype "passive"))
      (node (ref "RASPBERRYPI_GPIO") (pin "14") (pinfunction "14_14") (pintype "passive"))
      (node (ref "RASPBERRYPI_GPIO") (pin "20") (pinfunction "20_20") (pintype "passive"))
      (node (ref "RASPBERRYPI_GPIO") (pin "25") (pinfunction "25_25") (pintype "passive"))
      (node (ref "RASPBERRYPI_GPIO") (pin "30") (pinfunction "30_30") (pintype "passive"))
      (node (ref "RASPBERRYPI_GPIO") (pin "34") (pinfunction "34_34") (pintype "passive"))
      (node (ref "RASPBERRYPI_GPIO") (pin "39") (pinfunction "39_39") (pintype "passive"))
      (node (ref "RASPBERRYPI_GPIO") (pin "6") (pinfunction "6_6") (pintype "passive"))
      (node (ref "RASPBERRYPI_GPIO") (pin "9") (pinfunction "9_9") (pintype "passive"))
      (node (ref "SV1") (pin "3") (pinfunction "3_3") (pintype "passive"))
      (node (ref "SV1") (pin "4") (pinfunction "4_4") (pintype "passive"))
      (node (ref "SV1") (pin "5") (pinfunction "5_5") (pintype "passive"))
      (node (ref "SV1") (pin "6") (pinfunction "6_6") (pintype "passive"))
      (node (ref "SV1") (pin "7") (pinfunction "7_7") (pintype "passive"))
      (node (ref "SV1") (pin "8") (pinfunction "8_8") (pintype "passive"))
      (node (ref "TRIG0") (pin "P$1_SLEEVE") (pinfunction "SLEEVE_P$1_SLEEVE") (pintype "passive"))
      (node (ref "TRIG1") (pin "P$1_SLEEVE") (pinfunction "SLEEVE_P$1_SLEEVE") (pintype "passive"))
      (node (ref "TRIG2") (pin "P$1_SLEEVE") (pinfunction "SLEEVE_P$1_SLEEVE") (pintype "passive"))
      (node (ref "TRIG3") (pin "P$1_SLEEVE") (pinfunction "SLEEVE_P$1_SLEEVE") (pintype "passive"))
      (node (ref "TRIG4") (pin "P$1_SLEEVE") (pinfunction "SLEEVE_P$1_SLEEVE") (pintype "passive"))
      (node (ref "TRIG5") (pin "P$1_SLEEVE") (pinfunction "SLEEVE_P$1_SLEEVE") (pintype "passive"))
      (node (ref "TRIG6") (pin "P$1_SLEEVE") (pinfunction "SLEEVE_P$1_SLEEVE") (pintype "passive"))
      (node (ref "TRIG7") (pin "P$1_SLEEVE") (pinfunction "SLEEVE_P$1_SLEEVE") (pintype "passive"))
      (node (ref "TRIGS0") (pin "3") (pinfunction "S_3") (pintype "passive"))
      (node (ref "TRIGS1") (pin "3") (pinfunction "S_3") (pintype "passive"))
      (node (ref "TRIGS2") (pin "3") (pinfunction "S_3") (pintype "passive"))
      (node (ref "TRIGS3") (pin "3") (pinfunction "S_3") (pintype "passive"))
      (node (ref "TRIGS4") (pin "3") (pinfunction "S_3") (pintype "passive"))
      (node (ref "TRIGS5") (pin "3") (pinfunction "S_3") (pintype "passive"))
      (node (ref "TRIGS6") (pin "3") (pinfunction "S_3") (pintype "passive"))
      (node (ref "TRIGS7") (pin "3") (pinfunction "S_3") (pintype "passive"))
      (node (ref "ULN2803") (pin "9") (pinfunction "GND_9") (pintype "power_in"))
    )
    (net (code "22") (name "GPIO2") (class "Default")
      (node (ref "RASPBERRYPI_GPIO") (pin "3") (pinfunction "3_3") (pintype "passive"))
    )
    (net (code "23") (name "GPIO3") (class "Default")
      (node (ref "RASPBERRYPI_GPIO") (pin "5") (pinfunction "5_5") (pintype "passive"))
    )
    (net (code "24") (name "GPIO4") (class "Default")
      (node (ref "RASPBERRYPI_GPIO") (pin "7") (pinfunction "7_7") (pintype "passive"))
    )
    (net (code "25") (name "GPIO5") (class "Default")
      (node (ref "RASPBERRYPI_GPIO") (pin "29") (pinfunction "29_29") (pintype "passive"))
    )
    (net (code "26") (name "GPIO6") (class "Default")
      (node (ref "RASPBERRYPI_GPIO") (pin "31") (pinfunction "31_31") (pintype "passive"))
    )
    (net (code "27") (name "GPIO7") (class "Default")
      (node (ref "RASPBERRYPI_GPIO") (pin "26") (pinfunction "26_26") (pintype "passive"))
    )
    (net (code "28") (name "GPIO8") (class "Default")
      (node (ref "MCP3008") (pin "10") (pinfunction "~{CS}_10") (pintype "input"))
      (node (ref "RASPBERRYPI_GPIO") (pin "24") (pinfunction "24_24") (pintype "passive"))
    )
    (net (code "29") (name "GPIO9") (class "Default")
      (node (ref "MCP3008") (pin "12") (pinfunction "MISO_12") (pintype "output"))
      (node (ref "RASPBERRYPI_GPIO") (pin "21") (pinfunction "21_21") (pintype "passive"))
    )
    (net (code "30") (name "GPIO10") (class "Default")
      (node (ref "MCP3008") (pin "11") (pinfunction "MOSI_11") (pintype "input"))
      (node (ref "RASPBERRYPI_GPIO") (pin "19") (pinfunction "19_19") (pintype "passive"))
    )
    (net (code "31") (name "GPIO11") (class "Default")
      (node (ref "MCP3008") (pin "13") (pinfunction "SCK_13") (pintype "input"))
      (node (ref "RASPBERRYPI_GPIO") (pin "23") (pinfunction "23_23") (pintype "passive"))
    )
    (net (code "32") (name "GPIO12") (class "Default")
      (node (ref "RASPBERRYPI_GPIO") (pin "32") (pinfunction "32_32") (pintype "passive"))
    )
    (net (code "33") (name "GPIO13") (class "Default")
      (node (ref "RASPBERRYPI_GPIO") (pin "33") (pinfunction "33_33") (pintype "passive"))
    )
    (net (code "34") (name "GPIO14") (class "Default")
      (node (ref "MUX") (pin "11") (pinfunction "A_11") (pintype "input"))
      (node (ref "RASPBERRYPI_GPIO") (pin "8") (pinfunction "8_8") (pintype "passive"))
    )
    (net (code "35") (name "GPIO15") (class "Default")
      (node (ref "MUX") (pin "10") (pinfunction "B_10") (pintype "input"))
      (node (ref "RASPBERRYPI_GPIO") (pin "10") (pinfunction "10_10") (pintype "passive"))
    )
    (net (code "36") (name "GPIO16") (class "Default")
      (node (ref "RASPBERRYPI_GPIO") (pin "36") (pinfunction "36_36") (pintype "passive"))
    )
    (net (code "37") (name "GPIO17") (class "Default")
      (node (ref "MUX") (pin "3") (pinfunction "X_3") (pintype "bidirectional"))
      (node (ref "RASPBERRYPI_GPIO") (pin "11") (pinfunction "11_11") (pintype "passive"))
    )
    (net (code "38") (name "GPIO18") (class "Default")
      (node (ref "MUX") (pin "9") (pinfunction "C_9") (pintype "input"))
      (node (ref "RASPBERRYPI_GPIO") (pin "12") (pinfunction "12_12") (pintype "passive"))
    )
    (net (code "39") (name "GPIO19") (class "Default")
      (node (ref "RASPBERRYPI_GPIO") (pin "35") (pinfunction "35_35") (pintype "passive"))
    )
    (net (code "40") (name "GPIO20") (class "Default")
      (node (ref "RASPBERRYPI_GPIO") (pin "38") (pinfunction "38_38") (pintype "passive"))
    )
    (net (code "41") (name "GPIO21") (class "Default")
      (node (ref "RASPBERRYPI_GPIO") (pin "40") (pinfunction "40_40") (pintype "passive"))
    )
    (net (code "42") (name "GPIO22") (class "Default")
      (node (ref "RASPBERRYPI_GPIO") (pin "15") (pinfunction "15_15") (pintype "passive"))
    )
    (net (code "43") (name "GPIO23") (class "Default")
      (node (ref "R61") (pin "P$1") (pinfunction "1_P$1") (pintype "passive"))
      (node (ref "R62") (pin "P$1") (pinfunction "1_P$1") (pintype "passive"))
      (node (ref "RASPBERRYPI_GPIO") (pin "16") (pinfunction "16_16") (pintype "passive"))
    )
    (net (code "44") (name "GPIO24") (class "Default")
      (node (ref "RASPBERRYPI_GPIO") (pin "18") (pinfunction "18_18") (pintype "passive"))
    )
    (net (code "45") (name "GPIO25") (class "Default")
      (node (ref "RASPBERRYPI_GPIO") (pin "22") (pinfunction "22_22") (pintype "passive"))
    )
    (net (code "46") (name "GPIO26") (class "Default")
      (node (ref "RASPBERRYPI_GPIO") (pin "37") (pinfunction "37_37") (pintype "passive"))
    )
    (net (code "47") (name "GPIO27") (class "Default")
      (node (ref "RASPBERRYPI_GPIO") (pin "13") (pinfunction "13_13") (pintype "passive"))
    )
    (net (code "48") (name "MUX_0") (class "Default")
      (node (ref "COMPB_") (pin "2") (pinfunction "OUT_2") (pintype "output"))
      (node (ref "MUX") (pin "13") (pinfunction "X0_13") (pintype "bidirectional"))
      (node (ref "R29") (pin "P$1") (pinfunction "1_P$1") (pintype "passive"))
      (node (ref "R45") (pin "P$1") (pinfunction "1_P$1") (pintype "passive"))
    )
    (net (code "49") (name "MUX_1") (class "Default")
      (node (ref "COMPB_") (pin "1") (pinfunction "OUT_1") (pintype "output"))
      (node (ref "MUX") (pin "14") (pinfunction "X1_14") (pintype "bidirectional"))
      (node (ref "R30") (pin "P$1") (pinfunction "1_P$1") (pintype "passive"))
      (node (ref "R46") (pin "P$1") (pinfunction "1_P$1") (pintype "passive"))
    )
    (net (code "50") (name "MUX_2") (class "Default")
      (node (ref "COMPB_") (pin "14") (pinfunction "OUT_14") (pintype "output"))
      (node (ref "MUX") (pin "15") (pinfunction "X2_15") (pintype "bidirectional"))
      (node (ref "R31") (pin "P$1") (pinfunction "1_P$1") (pintype "passive"))
      (node (ref "R47") (pin "P$1") (pinfunction "1_P$1") (pintype "passive"))
    )
    (net (code "51") (name "MUX_3") (class "Default")
      (node (ref "COMPB_") (pin "13") (pinfunction "OUT_13") (pintype "output"))
      (node (ref "MUX") (pin "12") (pinfunction "X3_12") (pintype "bidirectional"))
      (node (ref "R32") (pin "P$1") (pinfunction "1_P$1") (pintype "passive"))
      (node (ref "R48") (pin "P$1") (pinfunction "1_P$1") (pintype "passive"))
    )
    (net (code "52") (name "MUX_4") (class "Default")
      (node (ref "COMPA_") (pin "2") (pinfunction "OUT_2") (pintype "output"))
      (node (ref "MUX") (pin "1") (pinfunction "X4_1") (pintype "bidirectional"))
      (node (ref "R33") (pin "P$1") (pinfunction "1_P$1") (pintype "passive"))
      (node (ref "R49") (pin "P$1") (pinfunction "1_P$1") (pintype "passive"))
    )
    (net (code "53") (name "MUX_5") (class "Default")
      (node (ref "COMPA_") (pin "1") (pinfunction "OUT_1") (pintype "output"))
      (node (ref "MUX") (pin "5") (pinfunction "X5_5") (pintype "bidirectional"))
      (node (ref "R34") (pin "P$1") (pinfunction "1_P$1") (pintype "passive"))
      (node (ref "R50") (pin "P$1") (pinfunction "1_P$1") (pintype "passive"))
    )
    (net (code "54") (name "MUX_6") (class "Default")
      (node (ref "COMPA_") (pin "14") (pinfunction "OUT_14") (pintype "output"))
      (node (ref "MUX") (pin "2") (pinfunction "X6_2") (pintype "bidirectional"))
      (node (ref "R35") (pin "P$1") (pinfunction "1_P$1") (pintype "passive"))
      (node (ref "R51") (pin "P$1") (pinfunction "1_P$1") (pintype "passive"))
    )
    (net (code "55") (name "MUX_7") (class "Default")
      (node (ref "COMPA_") (pin "13") (pinfunction "OUT_13") (pintype "output"))
      (node (ref "MUX") (pin "4") (pinfunction "X7_4") (pintype "bidirectional"))
      (node (ref "R36") (pin "P$1") (pinfunction "1_P$1") (pintype "passive"))
      (node (ref "R52") (pin "P$1") (pinfunction "1_P$1") (pintype "passive"))
    )
    (net (code "56") (name "Net-(COMPA_A-+IN)") (class "Default")
      (node (ref "COMPA_") (pin "5") (pinfunction "+IN_5") (pintype "input"))
      (node (ref "D13") (pin "C") (pinfunction "C_C") (pintype "passive"))
      (node (ref "TRIG4") (pin "P$3_TIP") (pinfunction "TIP_P$3_TIP") (pintype "passive"))
    )
    (net (code "57") (name "Net-(COMPA_B-+IN)") (class "Default")
      (node (ref "COMPA_") (pin "7") (pinfunction "+IN_7") (pintype "input"))
      (node (ref "D14") (pin "C") (pinfunction "C_C") (pintype "passive"))
      (node (ref "TRIG5") (pin "P$3_TIP") (pinfunction "TIP_P$3_TIP") (pintype "passive"))
    )
    (net (code "58") (name "Net-(COMPA_C-+IN)") (class "Default")
      (node (ref "COMPA_") (pin "9") (pinfunction "+IN_9") (pintype "input"))
      (node (ref "D15") (pin "C") (pinfunction "C_C") (pintype "passive"))
      (node (ref "TRIG6") (pin "P$3_TIP") (pinfunction "TIP_P$3_TIP") (pintype "passive"))
    )
    (net (code "59") (name "Net-(COMPA_D-+IN)") (class "Default")
      (node (ref "COMPA_") (pin "11") (pinfunction "+IN_11") (pintype "input"))
      (node (ref "D16") (pin "C") (pinfunction "C_C") (pintype "passive"))
      (node (ref "TRIG7") (pin "P$3_TIP") (pinfunction "TIP_P$3_TIP") (pintype "passive"))
    )
    (net (code "60") (name "Net-(COMPB_A-+IN)") (class "Default")
      (node (ref "COMPB_") (pin "5") (pinfunction "+IN_5") (pintype "input"))
      (node (ref "D9") (pin "C") (pinfunction "C_C") (pintype "passive"))
      (node (ref "TRIG0") (pin "P$3_TIP") (pinfunction "TIP_P$3_TIP") (pintype "passive"))
    )
    (net (code "61") (name "Net-(COMPB_B-+IN)") (class "Default")
      (node (ref "COMPB_") (pin "7") (pinfunction "+IN_7") (pintype "input"))
      (node (ref "D10") (pin "C") (pinfunction "C_C") (pintype "passive"))
      (node (ref "TRIG1") (pin "P$3_TIP") (pinfunction "TIP_P$3_TIP") (pintype "passive"))
    )
    (net (code "62") (name "Net-(COMPB_C-+IN)") (class "Default")
      (node (ref "COMPB_") (pin "9") (pinfunction "+IN_9") (pintype "input"))
      (node (ref "D11") (pin "C") (pinfunction "C_C") (pintype "passive"))
      (node (ref "TRIG2") (pin "P$3_TIP") (pinfunction "TIP_P$3_TIP") (pintype "passive"))
    )
    (net (code "63") (name "Net-(COMPB_D-+IN)") (class "Default")
      (node (ref "COMPB_") (pin "11") (pinfunction "+IN_11") (pintype "input"))
      (node (ref "D12") (pin "C") (pinfunction "C_C") (pintype "passive"))
      (node (ref "TRIG3") (pin "P$3_TIP") (pinfunction "TIP_P$3_TIP") (pintype "passive"))
    )
    (net (code "64") (name "Net-(CVIN_0-TIP)") (class "Default")
      (node (ref "CVIN_0") (pin "P$3_TIP") (pinfunction "TIP_P$3_TIP") (pintype "passive"))
      (node (ref "R14") (pin "P$1") (pinfunction "1_P$1") (pintype "passive"))
    )
    (net (code "65") (name "Net-(CVIN_1-TIP)") (class "Default")
      (node (ref "CVIN_1") (pin "P$3_TIP") (pinfunction "TIP_P$3_TIP") (pintype "passive"))
      (node (ref "R19") (pin "P$1") (pinfunction "1_P$1") (pintype "passive"))
    )
    (net (code "66") (name "Net-(CVIN_2-TIP)") (class "Default")
      (node (ref "CVIN_2") (pin "P$3_TIP") (pinfunction "TIP_P$3_TIP") (pintype "passive"))
      (node (ref "R23") (pin "P$1") (pinfunction "1_P$1") (pintype "passive"))
    )
    (net (code "67") (name "Net-(CVIN_3-TIP)") (class "Default")
      (node (ref "CVIN_3") (pin "P$3_TIP") (pinfunction "TIP_P$3_TIP") (pintype "passive"))
      (node (ref "R28") (pin "P$1") (pinfunction "1_P$1") (pintype "passive"))
    )
    (net (code "68") (name "Net-(D17-PadA)") (class "Default")
      (node (ref "D17") (pin "A") (pinfunction "A_A") (pintype "passive"))
      (node (ref "SV1") (pin "10") (pinfunction "10_10") (pintype "passive"))
      (node (ref "SV1") (pin "9") (pinfunction "9_9") (pintype "passive"))
    )
    (net (code "69") (name "Net-(D18-PadC)") (class "Default")
      (node (ref "D18") (pin "C") (pinfunction "C_C") (pintype "passive"))
      (node (ref "SV1") (pin "1") (pinfunction "1_1") (pintype "passive"))
      (node (ref "SV1") (pin "2") (pinfunction "2_2") (pintype "passive"))
    )
    (net (code "70") (name "Net-(LED1-C)") (class "Default")
      (node (ref "LED1") (pin "K") (pinfunction "C_K") (pintype "passive"))
      (node (ref "ULN2803") (pin "18") (pinfunction "O1_18") (pintype "open_collector"))
    )
    (net (code "71") (name "Net-(LED2-C)") (class "Default")
      (node (ref "LED2") (pin "K") (pinfunction "C_K") (pintype "passive"))
      (node (ref "ULN2803") (pin "17") (pinfunction "O2_17") (pintype "open_collector"))
    )
    (net (code "72") (name "Net-(LED3-C)") (class "Default")
      (node (ref "LED3") (pin "K") (pinfunction "C_K") (pintype "passive"))
      (node (ref "ULN2803") (pin "16") (pinfunction "O3_16") (pintype "open_collector"))
    )
    (net (code "73") (name "Net-(LED4-C)") (class "Default")
      (node (ref "LED4") (pin "K") (pinfunction "C_K") (pintype "passive"))
      (node (ref "ULN2803") (pin "15") (pinfunction "O4_15") (pintype "open_collector"))
    )
    (net (code "74") (name "Net-(LED5-C)") (class "Default")
      (node (ref "LED5") (pin "K") (pinfunction "C_K") (pintype "passive"))
      (node (ref "ULN2803") (pin "14") (pinfunction "O5_14") (pintype "open_collector"))
    )
    (net (code "75") (name "Net-(LED6-C)") (class "Default")
      (node (ref "LED6") (pin "K") (pinfunction "C_K") (pintype "passive"))
      (node (ref "ULN2803") (pin "13") (pinfunction "O6_13") (pintype "open_collector"))
    )
    (net (code "76") (name "Net-(LED7-C)") (class "Default")
      (node (ref "LED7") (pin "K") (pinfunction "C_K") (pintype "passive"))
      (node (ref "ULN2803") (pin "12") (pinfunction "O7_12") (pintype "open_collector"))
    )
    (net (code "77") (name "Net-(LED8-C)") (class "Default")
      (node (ref "LED8") (pin "K") (pinfunction "C_K") (pintype "passive"))
      (node (ref "ULN2803") (pin "11") (pinfunction "O8_11") (pintype "open_collector"))
    )
    (net (code "78") (name "Net-(OPAMPA_A-+IN)") (class "Default")
      (node (ref "OPAMPA_") (pin "3") (pinfunction "+IN_3") (pintype "input"))
      (node (ref "R14") (pin "P$2") (pinfunction "2_P$2") (pintype "passive"))
      (node (ref "R15") (pin "P$2") (pinfunction "2_P$2") (pintype "passive"))
    )
    (net (code "79") (name "Net-(OPAMPA_A--IN)") (class "Default")
      (node (ref "OPAMPA_") (pin "2") (pinfunction "-IN_2") (pintype "input"))
      (node (ref "R13") (pin "P$2") (pinfunction "2_P$2") (pintype "passive"))
      (node (ref "R16") (pin "P$1") (pinfunction "1_P$1") (pintype "passive"))
    )
    (net (code "80") (name "Net-(OPAMPA_B-+IN)") (class "Default")
      (node (ref "OPAMPA_") (pin "5") (pinfunction "+IN_5") (pintype "input"))
      (node (ref "R19") (pin "P$2") (pinfunction "2_P$2") (pintype "passive"))
      (node (ref "R20") (pin "P$2") (pinfunction "2_P$2") (pintype "passive"))
    )
    (net (code "81") (name "Net-(OPAMPA_B--IN)") (class "Default")
      (node (ref "OPAMPA_") (pin "6") (pinfunction "-IN_6") (pintype "input"))
      (node (ref "R17") (pin "P$1") (pinfunction "1_P$1") (pintype "passive"))
      (node (ref "R18") (pin "P$2") (pinfunction "2_P$2") (pintype "passive"))
    )
    (net (code "82") (name "Net-(OPAMPA_C-+IN)") (class "Default")
      (node (ref "OPAMPA_") (pin "10") (pinfunction "+IN_10") (pintype "input"))
      (node (ref "R22") (pin "P$2") (pinfunction "2_P$2") (pintype "passive"))
      (node (ref "R23") (pin "P$2") (pinfunction "2_P$2") (pintype "passive"))
    )
    (net (code "83") (name "Net-(OPAMPA_C--IN)") (class "Default")
      (node (ref "OPAMPA_") (pin "9") (pinfunction "-IN_9") (pintype "input"))
      (node (ref "R21") (pin "P$1") (pinfunction "1_P$1") (pintype "passive"))
      (node (ref "R24") (pin "P$2") (pinfunction "2_P$2") (pintype "passive"))
    )
    (net (code "84") (name "Net-(OPAMPA_D-+IN)") (class "Default")
      (node (ref "OPAMPA_") (pin "12") (pinfunction "+IN_12") (pintype "input"))
      (node (ref "R26") (pin "P$2") (pinfunction "2_P$2") (pintype "passive"))
      (node (ref "R28") (pin "P$2") (pinfunction "2_P$2") (pintype "passive"))
    )
    (net (code "85") (name "Net-(OPAMPA_D--IN)") (class "Default")
      (node (ref "OPAMPA_") (pin "13") (pinfunction "-IN_13") (pintype "input"))
      (node (ref "R25") (pin "P$1") (pinfunction "1_P$1") (pintype "passive"))
      (node (ref "R27") (pin "P$2") (pinfunction "2_P$2") (pintype "passive"))
    )
    (net (code "86") (name "Net-(PIDOWN-P)") (class "Default")
      (node (ref "PIDOWN") (pin "2") (pinfunction "P_2") (pintype "passive"))
      (node (ref "R61") (pin "P$2") (pinfunction "2_P$2") (pintype "passive"))
    )
    (net (code "87") (name "Net-(R3-2)") (class "Default")
      (node (ref "D1") (pin "A") (pinfunction "A_A") (pintype "passive"))
      (node (ref "D2") (pin "C") (pinfunction "C_C") (pintype "passive"))
      (node (ref "R3") (pin "P$2") (pinfunction "2_P$2") (pintype "passive"))
      (node (ref "R4") (pin "P$1") (pinfunction "1_P$1") (pintype "passive"))
    )
    (net (code "88") (name "Net-(R5-2)") (class "Default")
      (node (ref "D3") (pin "A") (pinfunction "A_A") (pintype "passive"))
      (node (ref "D4") (pin "C") (pinfunction "C_C") (pintype "passive"))
      (node (ref "R5") (pin "P$2") (pinfunction "2_P$2") (pintype "passive"))
      (node (ref "R6") (pin "P$1") (pinfunction "1_P$1") (pintype "passive"))
    )
    (net (code "89") (name "Net-(R7-2)") (class "Default")
      (node (ref "D5") (pin "A") (pinfunction "A_A") (pintype "passive"))
      (node (ref "D6") (pin "C") (pinfunction "C_C") (pintype "passive"))
      (node (ref "R7") (pin "P$2") (pinfunction "2_P$2") (pintype "passive"))
      (node (ref "R8") (pin "P$1") (pinfunction "1_P$1") (pintype "passive"))
    )
    (net (code "90") (name "Net-(R10-1)") (class "Default")
      (node (ref "D7") (pin "A") (pinfunction "A_A") (pintype "passive"))
      (node (ref "D8") (pin "C") (pinfunction "C_C") (pintype "passive"))
      (node (ref "R10") (pin "P$1") (pinfunction "1_P$1") (pintype "passive"))
      (node (ref "R9") (pin "P$2") (pinfunction "2_P$2") (pintype "passive"))
    )
    (net (code "91") (name "Net-(R37-2)") (class "Default")
      (node (ref "LED1") (pin "A") (pinfunction "A_A") (pintype "passive"))
      (node (ref "R37") (pin "P$2") (pinfunction "2_P$2") (pintype "passive"))
    )
    (net (code "92") (name "Net-(R38-2)") (class "Default")
      (node (ref "LED2") (pin "A") (pinfunction "A_A") (pintype "passive"))
      (node (ref "R38") (pin "P$2") (pinfunction "2_P$2") (pintype "passive"))
    )
    (net (code "93") (name "Net-(R39-2)") (class "Default")
      (node (ref "LED3") (pin "A") (pinfunction "A_A") (pintype "passive"))
      (node (ref "R39") (pin "P$2") (pinfunction "2_P$2") (pintype "passive"))
    )
    (net (code "94") (name "Net-(R40-2)") (class "Default")
      (node (ref "LED4") (pin "A") (pinfunction "A_A") (pintype "passive"))
      (node (ref "R40") (pin "P$2") (pinfunction "2_P$2") (pintype "passive"))
    )
    (net (code "95") (name "Net-(R41-2)") (class "Default")
      (node (ref "LED5") (pin "A") (pinfunction "A_A") (pintype "passive"))
      (node (ref "R41") (pin "P$2") (pinfunction "2_P$2") (pintype "passive"))
    )
    (net (code "96") (name "Net-(R42-1)") (class "Default")
      (node (ref "LED6") (pin "A") (pinfunction "A_A") (pintype "passive"))
      (node (ref "R42") (pin "P$1") (pinfunction "1_P$1") (pintype "passive"))
    )
    (net (code "97") (name "Net-(R43-1)") (class "Default")
      (node (ref "LED7") (pin "A") (pinfunction "A_A") (pintype "passive"))
      (node (ref "R43") (pin "P$1") (pinfunction "1_P$1") (pintype "passive"))
    )
    (net (code "98") (name "Net-(R44-1)") (class "Default")
      (node (ref "LED8") (pin "A") (pinfunction "A_A") (pintype "passive"))
      (node (ref "R44") (pin "P$1") (pinfunction "1_P$1") (pintype "passive"))
    )
    (net (code "99") (name "Net-(R45-2)") (class "Default")
      (node (ref "R45") (pin "P$2") (pinfunction "2_P$2") (pintype "passive"))
      (node (ref "ULN2803") (pin "1") (pinfunction "I1_1") (pintype "input"))
    )
    (net (code "100") (name "Net-(R46-2)") (class "Default")
      (node (ref "R46") (pin "P$2") (pinfunction "2_P$2") (pintype "passive"))
      (node (ref "ULN2803") (pin "2") (pinfunction "I2_2") (pintype "input"))
    )
    (net (code "101") (name "Net-(R47-2)") (class "Default")
      (node (ref "R47") (pin "P$2") (pinfunction "2_P$2") (pintype "passive"))
      (node (ref "ULN2803") (pin "3") (pinfunction "I3_3") (pintype "input"))
    )
    (net (code "102") (name "Net-(R48-2)") (class "Default")
      (node (ref "R48") (pin "P$2") (pinfunction "2_P$2") (pintype "passive"))
      (node (ref "ULN2803") (pin "4") (pinfunction "I4_4") (pintype "input"))
    )
    (net (code "103") (name "Net-(R49-2)") (class "Default")
      (node (ref "R49") (pin "P$2") (pinfunction "2_P$2") (pintype "passive"))
      (node (ref "ULN2803") (pin "5") (pinfunction "I5_5") (pintype "input"))
    )
    (net (code "104") (name "Net-(R50-2)") (class "Default")
      (node (ref "R50") (pin "P$2") (pinfunction "2_P$2") (pintype "passive"))
      (node (ref "ULN2803") (pin "6") (pinfunction "I6_6") (pintype "input"))
    )
    (net (code "105") (name "Net-(R51-2)") (class "Default")
      (node (ref "R51") (pin "P$2") (pinfunction "2_P$2") (pintype "passive"))
      (node (ref "ULN2803") (pin "7") (pinfunction "I7_7") (pintype "input"))
    )
    (net (code "106") (name "Net-(R52-2)") (class "Default")
      (node (ref "R52") (pin "P$2") (pinfunction "2_P$2") (pintype "passive"))
      (node (ref "ULN2803") (pin "8") (pinfunction "I8_8") (pintype "input"))
    )
    (net (code "107") (name "Net-(TRIG0-SWITCH)") (class "Default")
      (node (ref "TRIG0") (pin "P$2_SWITCH") (pinfunction "SWITCH_P$2_SWITCH") (pintype "passive"))
      (node (ref "TRIGS0") (pin "2") (pinfunction "P_2") (pintype "passive"))
    )
    (net (code "108") (name "Net-(TRIG1-SWITCH)") (class "Default")
      (node (ref "TRIG1") (pin "P$2_SWITCH") (pinfunction "SWITCH_P$2_SWITCH") (pintype "passive"))
      (node (ref "TRIGS1") (pin "2") (pinfunction "P_2") (pintype "passive"))
    )
    (net (code "109") (name "Net-(TRIG2-SWITCH)") (class "Default")
      (node (ref "TRIG2") (pin "P$2_SWITCH") (pinfunction "SWITCH_P$2_SWITCH") (pintype "passive"))
      (node (ref "TRIGS2") (pin "2") (pinfunction "P_2") (pintype "passive"))
    )
    (net (code "110") (name "Net-(TRIG3-SWITCH)") (class "Default")
      (node (ref "TRIG3") (pin "P$2_SWITCH") (pinfunction "SWITCH_P$2_SWITCH") (pintype "passive"))
      (node (ref "TRIGS3") (pin "2") (pinfunction "P_2") (pintype "passive"))
    )
    (net (code "111") (name "Net-(TRIG4-SWITCH)") (class "Default")
      (node (ref "TRIG4") (pin "P$2_SWITCH") (pinfunction "SWITCH_P$2_SWITCH") (pintype "passive"))
      (node (ref "TRIGS4") (pin "2") (pinfunction "P_2") (pintype "passive"))
    )
    (net (code "112") (name "Net-(TRIG5-SWITCH)") (class "Default")
      (node (ref "TRIG5") (pin "P$2_SWITCH") (pinfunction "SWITCH_P$2_SWITCH") (pintype "passive"))
      (node (ref "TRIGS5") (pin "2") (pinfunction "P_2") (pintype "passive"))
    )
    (net (code "113") (name "Net-(TRIG6-SWITCH)") (class "Default")
      (node (ref "TRIG6") (pin "P$2_SWITCH") (pinfunction "SWITCH_P$2_SWITCH") (pintype "passive"))
      (node (ref "TRIGS6") (pin "2") (pinfunction "P_2") (pintype "passive"))
    )
    (net (code "114") (name "Net-(TRIG7-SWITCH)") (class "Default")
      (node (ref "TRIG7") (pin "P$2_SWITCH") (pinfunction "SWITCH_P$2_SWITCH") (pintype "passive"))
      (node (ref "TRIGS7") (pin "2") (pinfunction "P_2") (pintype "passive"))
    )
    (net (code "115") (name "REF1V65") (class "Default")
      (node (ref "OPAMPB_") (pin "3") (pinfunction "+IN_3") (pintype "input"))
      (node (ref "R1") (pin "P$2") (pinfunction "2_P$2") (pintype "passive"))
      (node (ref "R2") (pin "P$1") (pinfunction "1_P$1") (pintype "passive"))
    )
    (net (code "116") (name "REF2V5") (class "Default")
      (node (ref "OPAMPB_") (pin "5") (pinfunction "+IN_5") (pintype "input"))
      (node (ref "R11") (pin "P$2") (pinfunction "2_P$2") (pintype "passive"))
      (node (ref "R12") (pin "P$1") (pinfunction "1_P$1") (pintype "passive"))
    )
    (net (code "117") (name "unconnected-(OPAMPB_C-+IN-Pad10)") (class "Default")
      (node (ref "OPAMPB_") (pin "10") (pinfunction "+IN_10") (pintype "input"))
    )
    (net (code "118") (name "unconnected-(OPAMPB_C--IN-Pad9)") (class "Default")
      (node (ref "OPAMPB_") (pin "9") (pinfunction "-IN_9") (pintype "input"))
    )
    (net (code "119") (name "unconnected-(OPAMPB_C-OUT-Pad8)") (class "Default")
      (node (ref "OPAMPB_") (pin "8") (pinfunction "OUT_8") (pintype "output"))
    )
    (net (code "120") (name "unconnected-(OPAMPB_D-+IN-Pad12)") (class "Default")
      (node (ref "OPAMPB_") (pin "12") (pinfunction "+IN_12") (pintype "input"))
    )
    (net (code "121") (name "unconnected-(OPAMPB_D--IN-Pad13)") (class "Default")
      (node (ref "OPAMPB_") (pin "13") (pinfunction "-IN_13") (pintype "input"))
    )
    (net (code "122") (name "unconnected-(OPAMPB_D-OUT-Pad14)") (class "Default")
      (node (ref "OPAMPB_") (pin "14") (pinfunction "OUT_14") (pintype "output"))
    )
  )
)
